# io.net
KiCad netlist of a schematic drawn in EAGLE
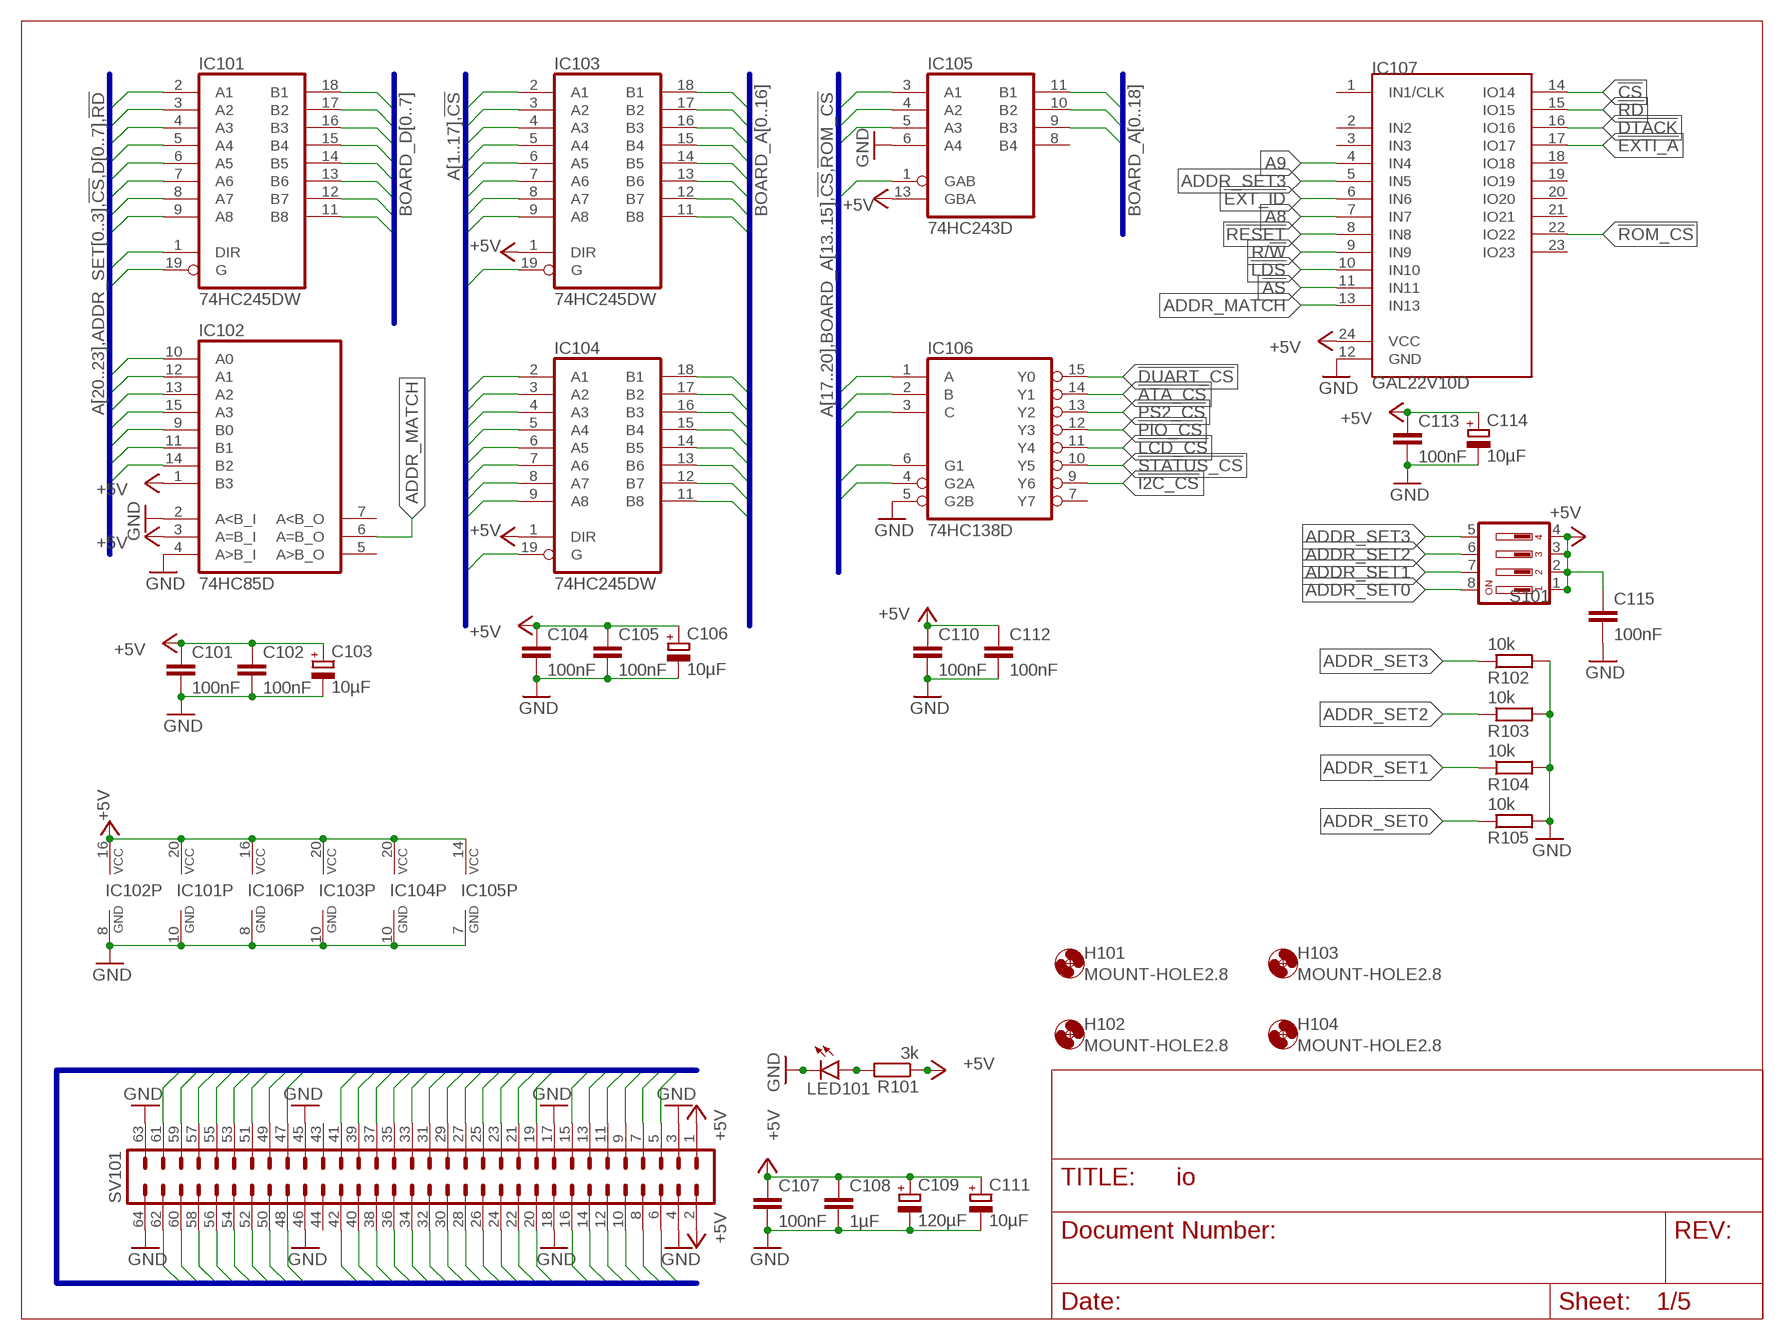
[diagram p0: schematic, sheet 1]
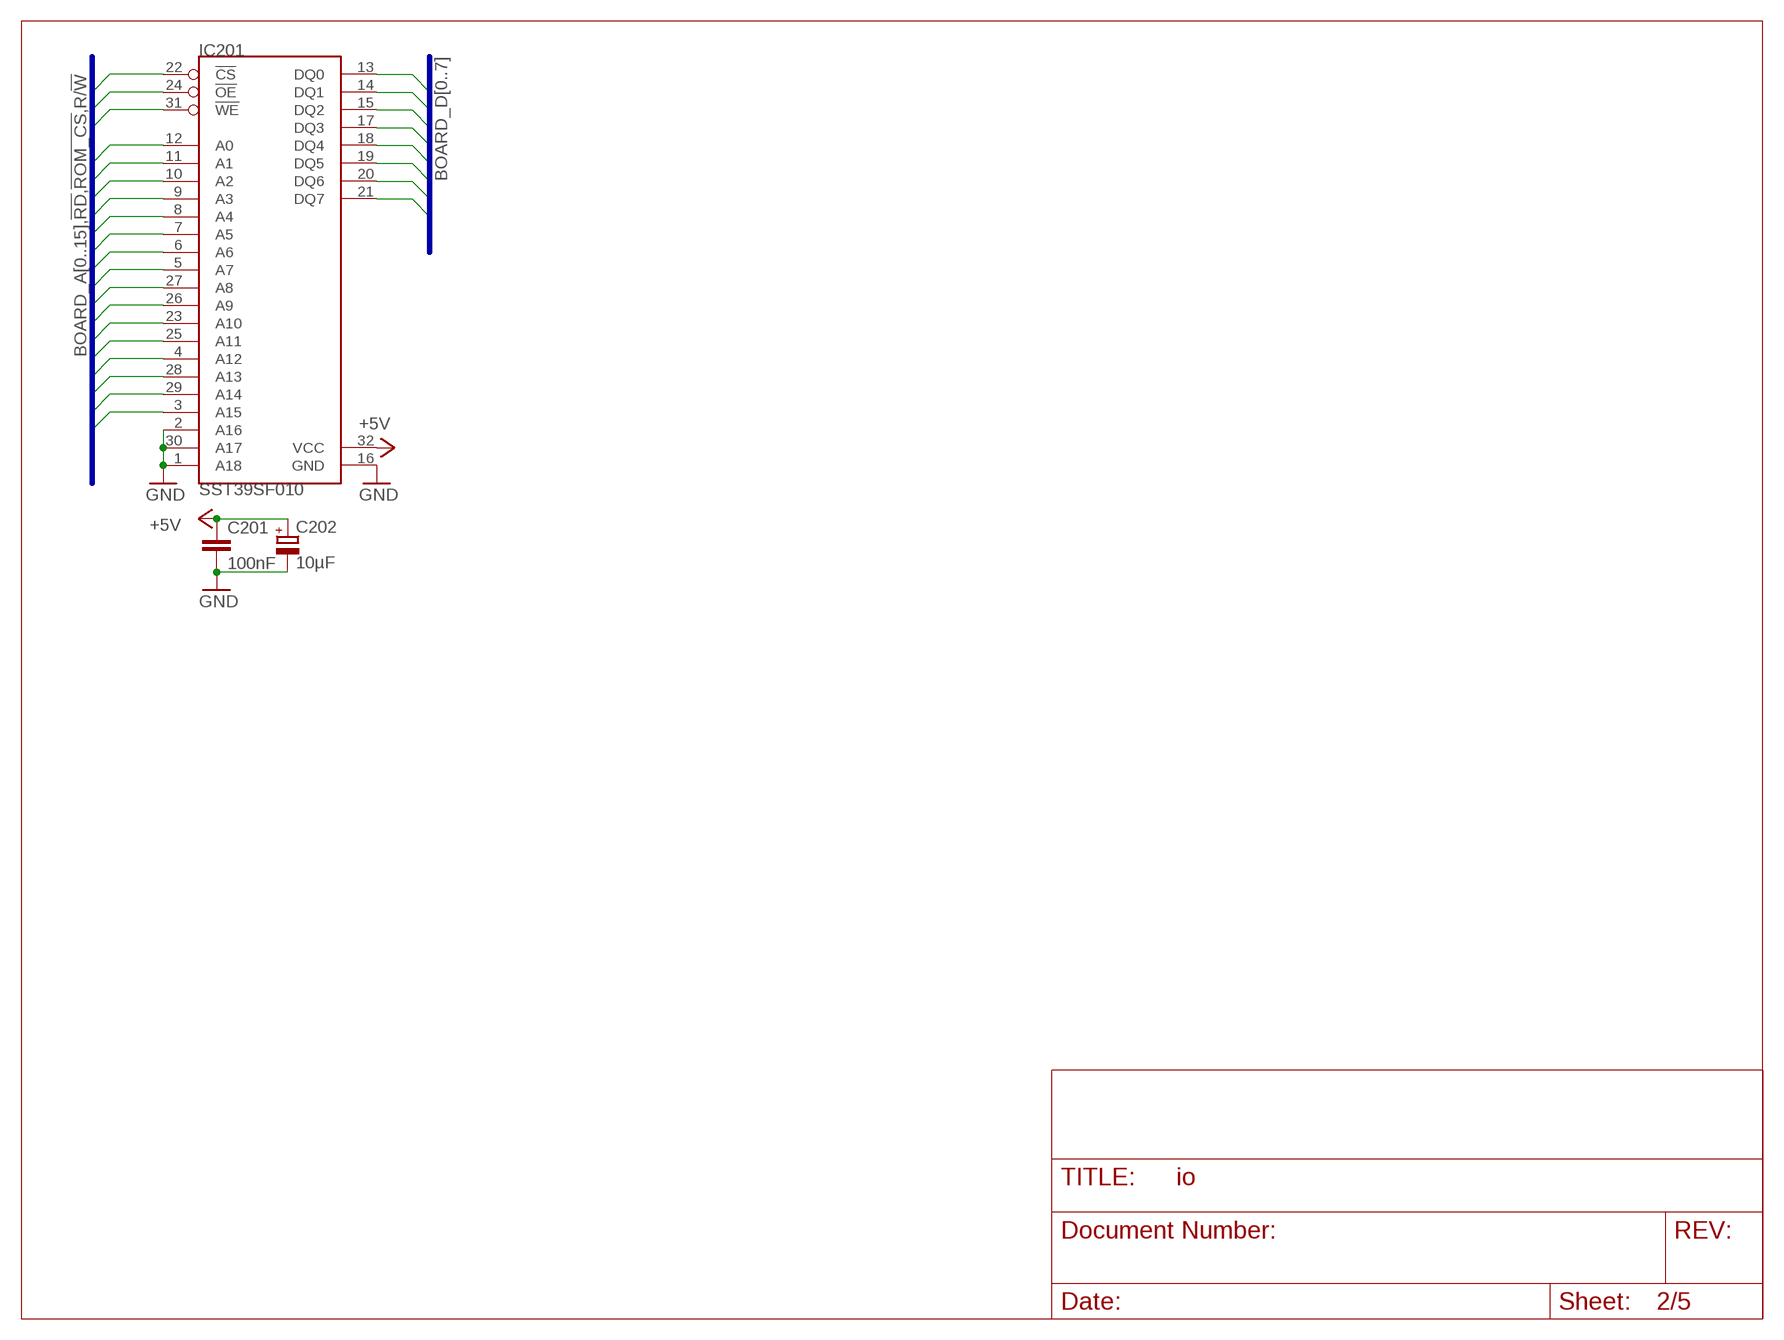
[diagram p1: schematic, sheet 2]
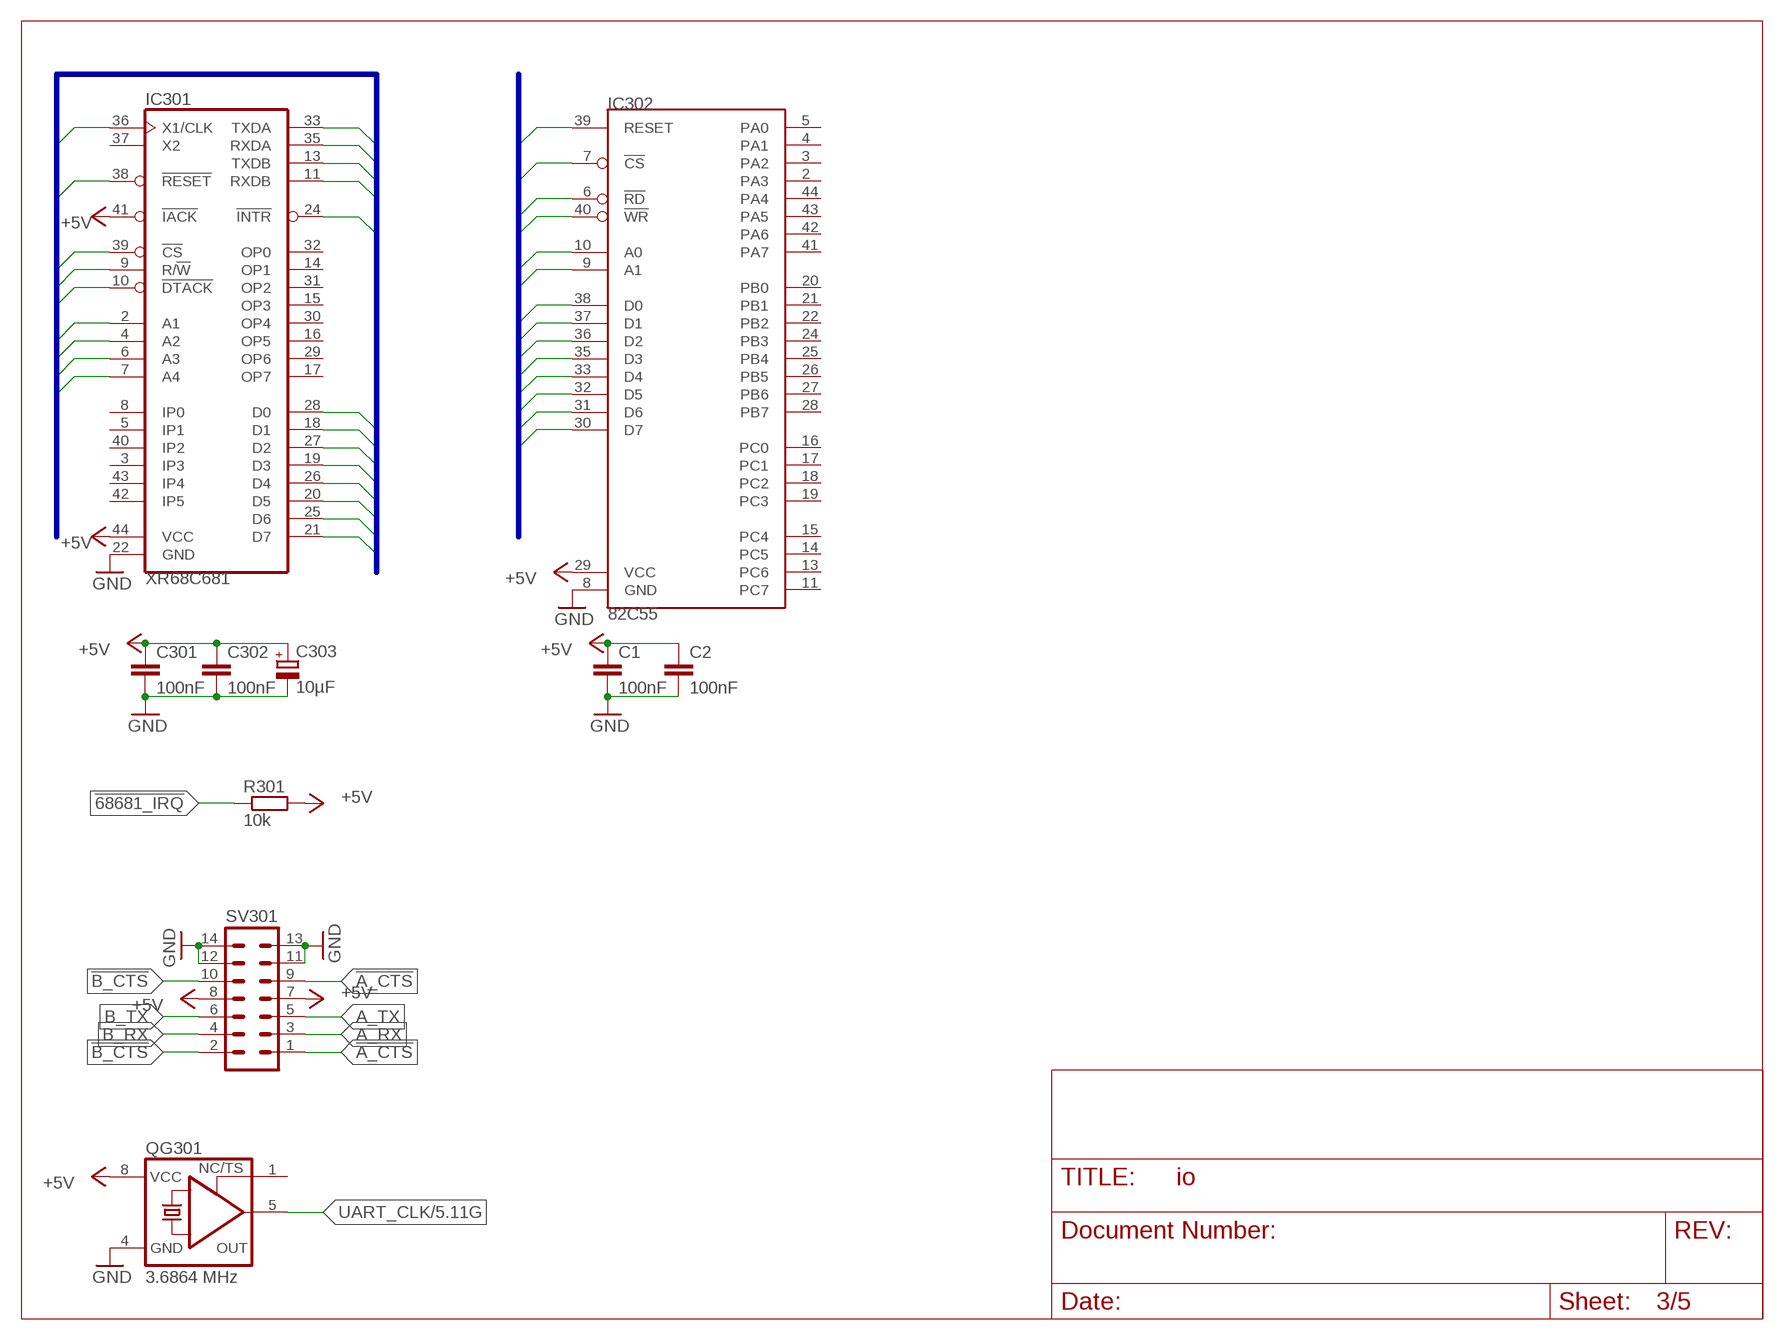
[diagram p2: schematic, sheet 3]
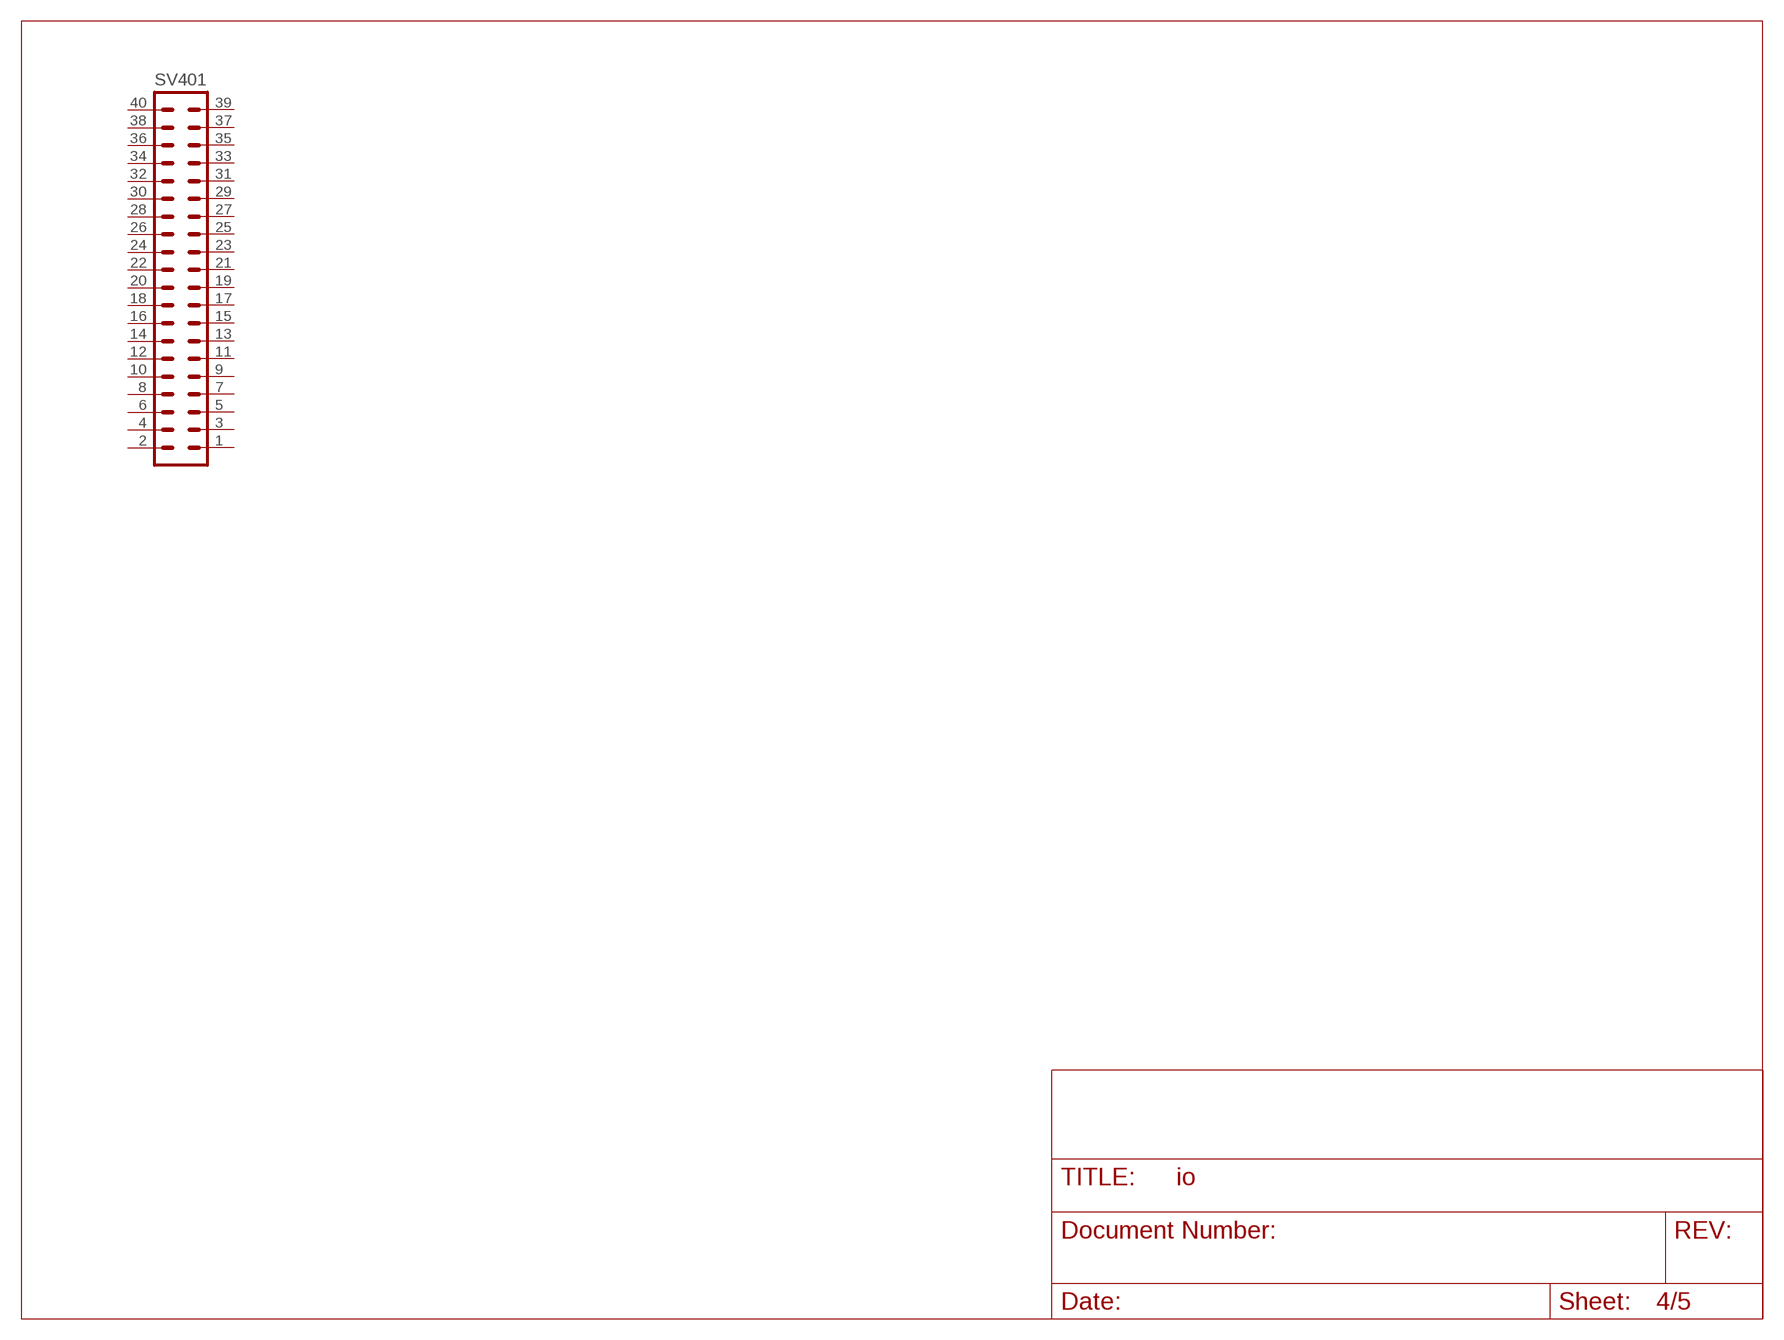
[diagram p3: schematic, sheet 4]
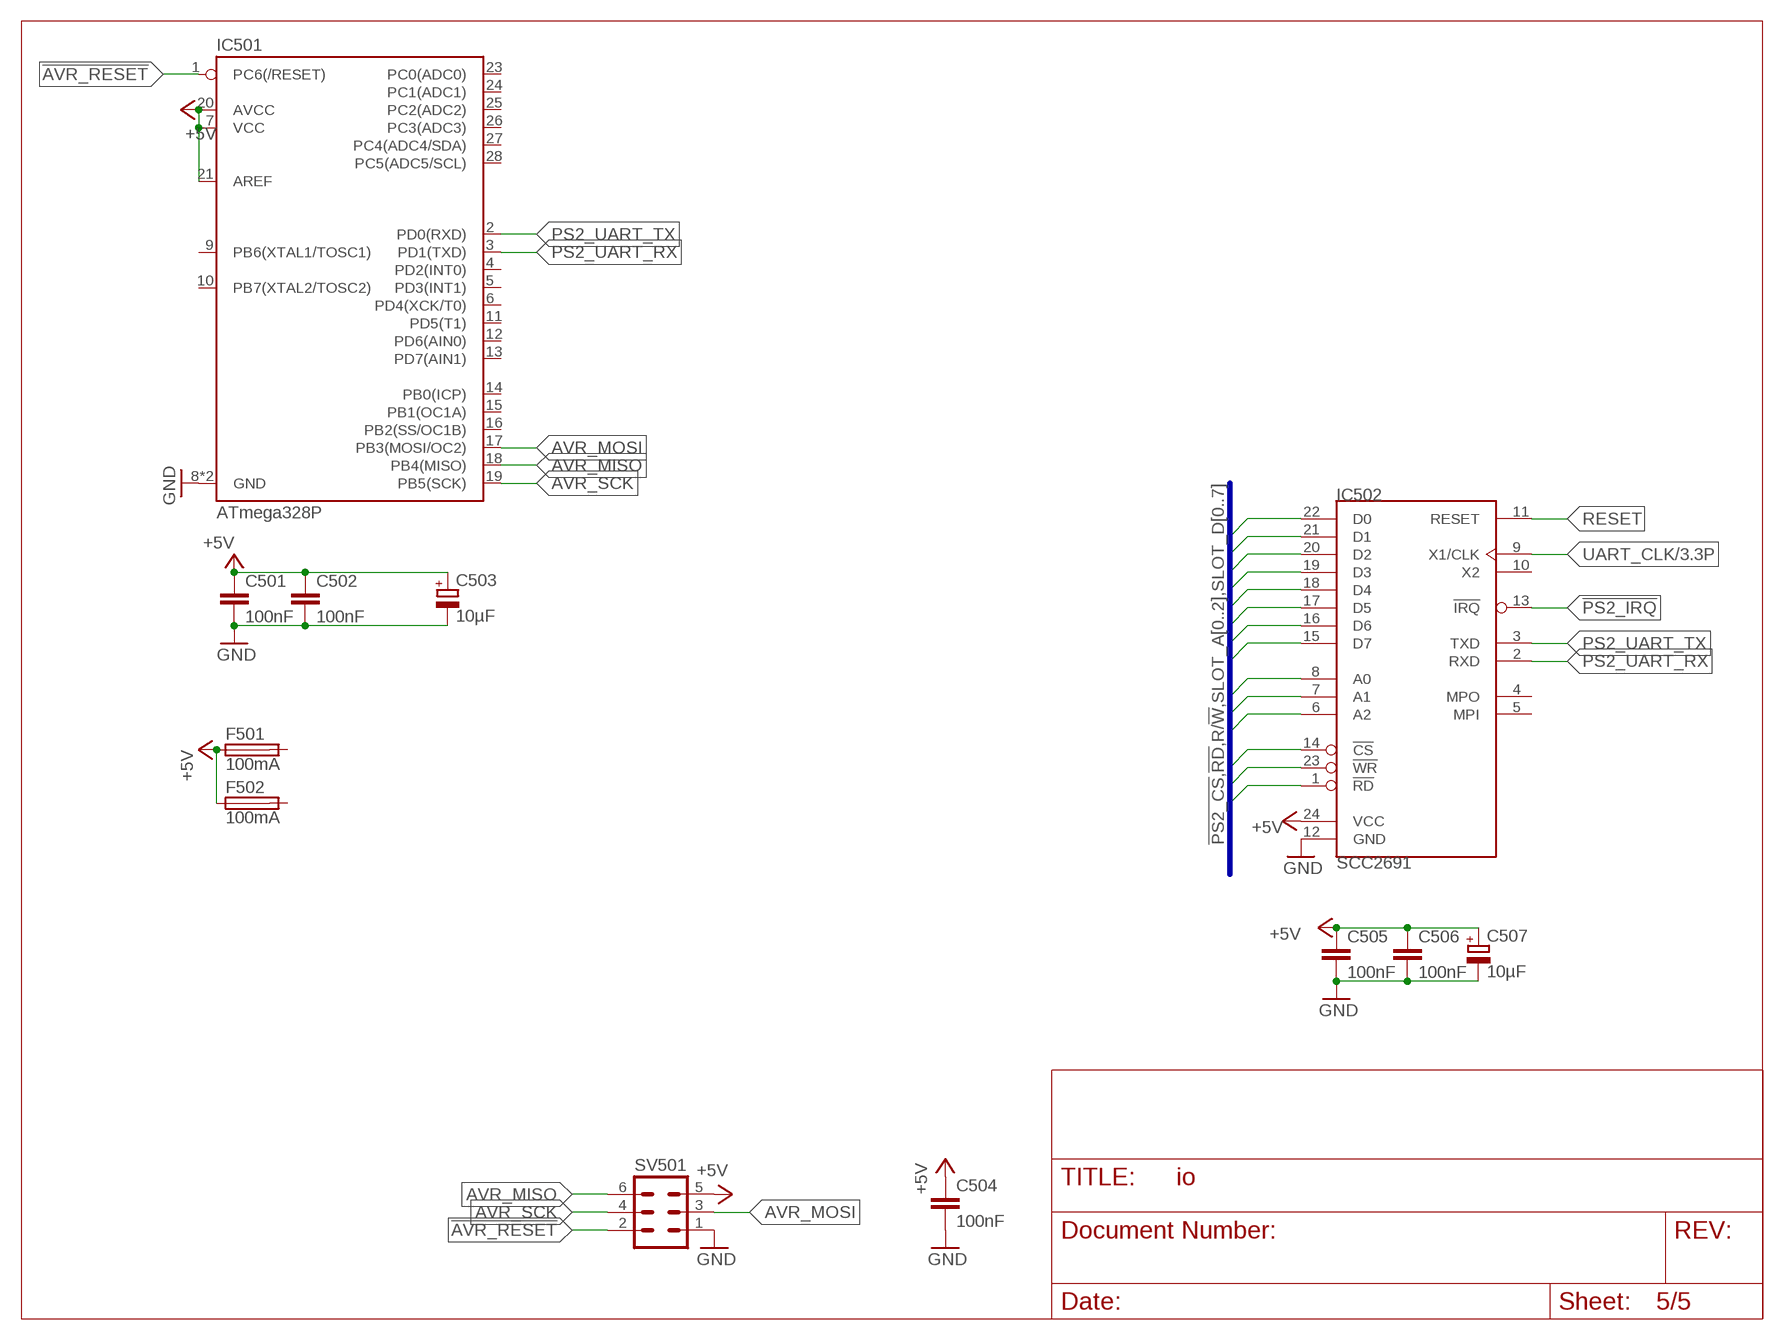
[diagram p4: schematic, sheet 5]

(export (version "E")
  (design (tool "Eeschema 10.0.6"))
  (components
    (comp (ref "C201")
      (value "100nF")
      (footprint "eagle-import:C0805")
      (libsource (lib "eagle-import") (part "C-EUC0805"))
    )
    (comp (ref "C202")
      (value "10µF")
      (footprint "eagle-import:SMC_B")
      (libsource (lib "eagle-import") (part "CPOL-EUSMCB"))
    )
    (comp (ref "IC201")
      (value "SST39SF010")
      (footprint "eagle-import:PLCC-S32")
      (libsource (lib "eagle-import") (part "SST39SF0X0PLCC32-SOCKET"))
    )
    (comp (ref "C1")
      (value "100nF")
      (footprint "eagle-import:C0805")
      (libsource (lib "eagle-import") (part "C-EUC0805"))
    )
    (comp (ref "C2")
      (value "100nF")
      (footprint "eagle-import:C0805")
      (libsource (lib "eagle-import") (part "C-EUC0805"))
    )
    (comp (ref "C301")
      (value "100nF")
      (footprint "eagle-import:C0805")
      (libsource (lib "eagle-import") (part "C-EUC0805"))
    )
    (comp (ref "C302")
      (value "100nF")
      (footprint "eagle-import:C0805")
      (libsource (lib "eagle-import") (part "C-EUC0805"))
    )
    (comp (ref "C303")
      (value "10µF")
      (footprint "eagle-import:SMC_B")
      (libsource (lib "eagle-import") (part "CPOL-EUSMCB"))
    )
    (comp (ref "IC301")
      (value "XR68C681")
      (footprint "eagle-import:PLCC-S44")
      (libsource (lib "eagle-import") (part "MC68681PLCC44-SOCKET"))
    )
    (comp (ref "IC302")
      (value "82C55")
      (footprint "eagle-import:PLCC-S44")
      (libsource (lib "eagle-import") (part "82C55PLCC44-SOCKET"))
    )
    (comp (ref "QG301")
      (value "3.6864 MHz")
      (footprint "eagle-import:DIL08S")
      (libsource (lib "eagle-import") (part "XO-8"))
    )
    (comp (ref "R301")
      (value "10k")
      (footprint "eagle-import:R2012")
      (libsource (lib "eagle-import") (part "R-EU_R2012"))
    )
    (comp (ref "SV301")
      (value "MA07-2W")
      (footprint "eagle-import:MA07-2W")
      (libsource (lib "eagle-import") (part "MA07-2W"))
    )
    (comp (ref "C101")
      (value "100nF")
      (footprint "eagle-import:C0805")
      (libsource (lib "eagle-import") (part "C-EUC0805"))
    )
    (comp (ref "C102")
      (value "100nF")
      (footprint "eagle-import:C0805")
      (libsource (lib "eagle-import") (part "C-EUC0805"))
    )
    (comp (ref "C103")
      (value "10µF")
      (footprint "eagle-import:SMC_B")
      (libsource (lib "eagle-import") (part "CPOL-EUSMCB"))
    )
    (comp (ref "C104")
      (value "100nF")
      (footprint "eagle-import:C0805")
      (libsource (lib "eagle-import") (part "C-EUC0805"))
    )
    (comp (ref "C105")
      (value "100nF")
      (footprint "eagle-import:C0805")
      (libsource (lib "eagle-import") (part "C-EUC0805"))
    )
    (comp (ref "C106")
      (value "10µF")
      (footprint "eagle-import:SMC_B")
      (libsource (lib "eagle-import") (part "CPOL-EUSMCB"))
    )
    (comp (ref "C107")
      (value "100nF")
      (footprint "eagle-import:C0805")
      (libsource (lib "eagle-import") (part "C-EUC0805"))
    )
    (comp (ref "C108")
      (value "1µF")
      (footprint "eagle-import:C0805")
      (libsource (lib "eagle-import") (part "C-EUC0805"))
    )
    (comp (ref "C109")
      (value "120µF")
      (footprint "eagle-import:E2,5-7")
      (libsource (lib "eagle-import") (part "CPOL-EUE2.5-7"))
    )
    (comp (ref "C110")
      (value "100nF")
      (footprint "eagle-import:C0805")
      (libsource (lib "eagle-import") (part "C-EUC0805"))
    )
    (comp (ref "C111")
      (value "10µF")
      (footprint "eagle-import:SMC_B")
      (libsource (lib "eagle-import") (part "CPOL-EUSMCB"))
    )
    (comp (ref "C112")
      (value "100nF")
      (footprint "eagle-import:C0805")
      (libsource (lib "eagle-import") (part "C-EUC0805"))
    )
    (comp (ref "C113")
      (value "100nF")
      (footprint "eagle-import:C0805")
      (libsource (lib "eagle-import") (part "C-EUC0805"))
    )
    (comp (ref "C114")
      (value "10µF")
      (footprint "eagle-import:SMC_B")
      (libsource (lib "eagle-import") (part "CPOL-EUSMCB"))
    )
    (comp (ref "C115")
      (value "100nF")
      (footprint "eagle-import:C0805")
      (libsource (lib "eagle-import") (part "C-EUC0805"))
    )
    (comp (ref "H101")
      (value "MOUNT-HOLE2.8")
      (footprint "eagle-import:2,8")
      (libsource (lib "eagle-import") (part "MOUNT-HOLE2.8"))
    )
    (comp (ref "H102")
      (value "MOUNT-HOLE2.8")
      (footprint "eagle-import:2,8")
      (libsource (lib "eagle-import") (part "MOUNT-HOLE2.8"))
    )
    (comp (ref "H103")
      (value "MOUNT-HOLE2.8")
      (footprint "eagle-import:2,8")
      (libsource (lib "eagle-import") (part "MOUNT-HOLE2.8"))
    )
    (comp (ref "H104")
      (value "MOUNT-HOLE2.8")
      (footprint "eagle-import:2,8")
      (libsource (lib "eagle-import") (part "MOUNT-HOLE2.8"))
    )
    (comp (ref "IC101")
      (value "74HC245DW")
      (footprint "eagle-import:SO20W")
      (fields (field (name "MOUSER") "595-SN74HC245DWR"))
      (libsource (lib "eagle-import") (part "74245DWHC"))
    )
    (comp (ref "IC102")
      (value "74HC85D")
      (footprint "eagle-import:SO16")
      (fields (field (name "MOUSER") "771-74HC138D"))
      (libsource (lib "eagle-import") (part "7485DHC"))
    )
    (comp (ref "IC103")
      (value "74HC245DW")
      (footprint "eagle-import:SO20W")
      (fields (field (name "MOUSER") "595-SN74HC245DWR"))
      (libsource (lib "eagle-import") (part "74245DWHC"))
    )
    (comp (ref "IC104")
      (value "74HC245DW")
      (footprint "eagle-import:SO20W")
      (fields (field (name "MOUSER") "595-SN74HC245DWR"))
      (libsource (lib "eagle-import") (part "74245DWHC"))
    )
    (comp (ref "IC105")
      (value "74HC243D")
      (footprint "eagle-import:SO14")
      (fields (field (name "MOUSER") "595-CD74HC243M96"))
      (libsource (lib "eagle-import") (part "74243DHC"))
    )
    (comp (ref "IC106")
      (value "74HC138D")
      (footprint "eagle-import:SO16")
      (fields (field (name "MOUSER") "595-SN74HC138DG4"))
      (libsource (lib "eagle-import") (part "74138DHC"))
    )
    (comp (ref "IC107")
      (value "GAL22V10D")
      (footprint "eagle-import:DIL24S")
      (libsource (lib "eagle-import") (part "GAL22V10DIP24"))
    )
    (comp (ref "LED101")
      (value "LEDCHIPLED_1206")
      (footprint "eagle-import:CHIPLED_1206")
      (libsource (lib "eagle-import") (part "LEDCHIPLED_1206"))
    )
    (comp (ref "R101")
      (value "3k")
      (footprint "eagle-import:R2012")
      (libsource (lib "eagle-import") (part "R-EU_R2012"))
    )
    (comp (ref "R102")
      (value "10k")
      (footprint "eagle-import:R2012")
      (libsource (lib "eagle-import") (part "R-EU_R2012"))
    )
    (comp (ref "R103")
      (value "10k")
      (footprint "eagle-import:R2012")
      (libsource (lib "eagle-import") (part "R-EU_R2012"))
    )
    (comp (ref "R104")
      (value "10k")
      (footprint "eagle-import:R2012")
      (libsource (lib "eagle-import") (part "R-EU_R2012"))
    )
    (comp (ref "R105")
      (value "10k")
      (footprint "eagle-import:R2012")
      (libsource (lib "eagle-import") (part "R-EU_R2012"))
    )
    (comp (ref "S101")
      (value "DP04")
      (footprint "eagle-import:DP-04")
      (libsource (lib "eagle-import") (part "DP04"))
    )
    (comp (ref "SV101")
      (value "ML64L")
      (footprint "eagle-import:ML64L")
      (libsource (lib "eagle-import") (part "ML64L"))
    )
    (comp (ref "C501")
      (value "100nF")
      (footprint "eagle-import:C0805")
      (libsource (lib "eagle-import") (part "C-EUC0805"))
    )
    (comp (ref "C502")
      (value "100nF")
      (footprint "eagle-import:C0805")
      (libsource (lib "eagle-import") (part "C-EUC0805"))
    )
    (comp (ref "C503")
      (value "10µF")
      (footprint "eagle-import:SMC_B")
      (libsource (lib "eagle-import") (part "CPOL-EUSMCB"))
    )
    (comp (ref "C504")
      (value "100nF")
      (footprint "eagle-import:C0805")
      (libsource (lib "eagle-import") (part "C-EUC0805"))
    )
    (comp (ref "C505")
      (value "100nF")
      (footprint "eagle-import:C0805")
      (libsource (lib "eagle-import") (part "C-EUC0805"))
    )
    (comp (ref "C506")
      (value "100nF")
      (footprint "eagle-import:C0805")
      (libsource (lib "eagle-import") (part "C-EUC0805"))
    )
    (comp (ref "C507")
      (value "10µF")
      (footprint "eagle-import:SMC_B")
      (libsource (lib "eagle-import") (part "CPOL-EUSMCB"))
    )
    (comp (ref "F501")
      (value "100mA")
      (footprint "eagle-import:WE-MI_1206")
      (libsource (lib "eagle-import") (part "FUSE1206"))
    )
    (comp (ref "F502")
      (value "100mA")
      (footprint "eagle-import:WE-MI_1206")
      (libsource (lib "eagle-import") (part "FUSE1206"))
    )
    (comp (ref "IC501")
      (value "ATmega328P")
      (footprint "eagle-import:DIP28")
      (libsource (lib "eagle-import") (part "ATMEGA328P_PDIP"))
    )
    (comp (ref "IC502")
      (value "SCC2691")
      (footprint "eagle-import:DIL24S")
      (libsource (lib "eagle-import") (part "SCC2691"))
    )
    (comp (ref "SV501")
      (value "ML6")
      (footprint "eagle-import:ML6")
      (libsource (lib "eagle-import") (part "ML6"))
    )
    (comp (ref "SV401")
      (value "ML40L")
      (footprint "eagle-import:ML40L")
      (libsource (lib "eagle-import") (part "ML40L"))
    )
  )
  (nets
    (net (code "4") (name "+5V") (class "Default")
      (node (ref "C1") (pin "1") (pinfunction "1_1") (pintype "passive"))
      (node (ref "C101") (pin "1") (pinfunction "1_1") (pintype "passive"))
      (node (ref "C102") (pin "1") (pinfunction "1_1") (pintype "passive"))
      (node (ref "C103") (pin "+") (pinfunction "+_+") (pintype "passive"))
      (node (ref "C104") (pin "1") (pinfunction "1_1") (pintype "passive"))
      (node (ref "C105") (pin "1") (pinfunction "1_1") (pintype "passive"))
      (node (ref "C106") (pin "+") (pinfunction "+_+") (pintype "passive"))
      (node (ref "C107") (pin "1") (pinfunction "1_1") (pintype "passive"))
      (node (ref "C108") (pin "1") (pinfunction "1_1") (pintype "passive"))
      (node (ref "C109") (pin "+") (pinfunction "+_+") (pintype "passive"))
      (node (ref "C110") (pin "1") (pinfunction "1_1") (pintype "passive"))
      (node (ref "C111") (pin "+") (pinfunction "+_+") (pintype "passive"))
      (node (ref "C112") (pin "1") (pinfunction "1_1") (pintype "passive"))
      (node (ref "C113") (pin "1") (pinfunction "1_1") (pintype "passive"))
      (node (ref "C114") (pin "+") (pinfunction "+_+") (pintype "passive"))
      (node (ref "C115") (pin "1") (pinfunction "1_1") (pintype "passive"))
      (node (ref "C2") (pin "1") (pinfunction "1_1") (pintype "passive"))
      (node (ref "C201") (pin "1") (pinfunction "1_1") (pintype "passive"))
      (node (ref "C202") (pin "+") (pinfunction "+_+") (pintype "passive"))
      (node (ref "C301") (pin "1") (pinfunction "1_1") (pintype "passive"))
      (node (ref "C302") (pin "1") (pinfunction "1_1") (pintype "passive"))
      (node (ref "C303") (pin "+") (pinfunction "+_+") (pintype "passive"))
      (node (ref "C501") (pin "1") (pinfunction "1_1") (pintype "passive"))
      (node (ref "C502") (pin "1") (pinfunction "1_1") (pintype "passive"))
      (node (ref "C503") (pin "+") (pinfunction "+_+") (pintype "passive"))
      (node (ref "C504") (pin "1") (pinfunction "1_1") (pintype "passive"))
      (node (ref "C505") (pin "1") (pinfunction "1_1") (pintype "passive"))
      (node (ref "C506") (pin "1") (pinfunction "1_1") (pintype "passive"))
      (node (ref "C507") (pin "+") (pinfunction "+_+") (pintype "passive"))
      (node (ref "F501") (pin "1") (pinfunction "1_1") (pintype "passive"))
      (node (ref "F502") (pin "1") (pinfunction "1_1") (pintype "passive"))
      (node (ref "IC101") (pin "20") (pinfunction "VCC_20") (pintype "power_in"))
      (node (ref "IC102") (pin "1") (pinfunction "B3_1") (pintype "input"))
      (node (ref "IC102") (pin "16") (pinfunction "VCC_16") (pintype "power_in"))
      (node (ref "IC102") (pin "3") (pinfunction "A=B_I_3") (pintype "input"))
      (node (ref "IC103") (pin "1") (pinfunction "DIR_1") (pintype "input"))
      (node (ref "IC103") (pin "20") (pinfunction "VCC_20") (pintype "power_in"))
      (node (ref "IC104") (pin "1") (pinfunction "DIR_1") (pintype "input"))
      (node (ref "IC104") (pin "20") (pinfunction "VCC_20") (pintype "power_in"))
      (node (ref "IC105") (pin "13") (pinfunction "GBA_13") (pintype "input"))
      (node (ref "IC105") (pin "14") (pinfunction "VCC_14") (pintype "power_in"))
      (node (ref "IC106") (pin "16") (pinfunction "VCC_16") (pintype "power_in"))
      (node (ref "IC107") (pin "24") (pinfunction "VCC_24") (pintype "power_in"))
      (node (ref "IC201") (pin "32") (pinfunction "VCC_32") (pintype "power_in"))
      (node (ref "IC301") (pin "41") (pinfunction "~{IACK}_41") (pintype "input"))
      (node (ref "IC301") (pin "44") (pinfunction "VCC_44") (pintype "power_in"))
      (node (ref "IC302") (pin "29") (pinfunction "VCC_29") (pintype "power_in"))
      (node (ref "IC501") (pin "20") (pinfunction "AVCC_20") (pintype "bidirectional"))
      (node (ref "IC501") (pin "21") (pinfunction "AREF_21") (pintype "bidirectional"))
      (node (ref "IC501") (pin "7") (pinfunction "VCC_7") (pintype "bidirectional"))
      (node (ref "IC502") (pin "24") (pinfunction "VCC_24") (pintype "power_in"))
      (node (ref "QG301") (pin "8") (pinfunction "VCC_8") (pintype "power_in"))
      (node (ref "R101") (pin "1") (pinfunction "1_1") (pintype "passive"))
      (node (ref "R301") (pin "2") (pinfunction "2_2") (pintype "passive"))
      (node (ref "S101") (pin "1") (pinfunction "1_1") (pintype "passive"))
      (node (ref "S101") (pin "2") (pinfunction "2_2") (pintype "passive"))
      (node (ref "S101") (pin "3") (pinfunction "3_3") (pintype "passive"))
      (node (ref "S101") (pin "4") (pinfunction "4_4") (pintype "passive"))
      (node (ref "SV101") (pin "1") (pinfunction "1_1") (pintype "passive"))
      (node (ref "SV101") (pin "2") (pinfunction "2_2") (pintype "passive"))
      (node (ref "SV301") (pin "7") (pinfunction "7_7") (pintype "passive"))
      (node (ref "SV301") (pin "8") (pinfunction "8_8") (pintype "passive"))
      (node (ref "SV501") (pin "5") (pinfunction "5_5") (pintype "passive"))
    )
    (net (code "14") (name "A1") (class "Default")
      (node (ref "IC103") (pin "2") (pinfunction "A1_2") (pintype "bidirectional"))
      (node (ref "SV101") (pin "20") (pinfunction "20_20") (pintype "passive"))
    )
    (net (code "15") (name "A2") (class "Default")
      (node (ref "IC103") (pin "3") (pinfunction "A2_3") (pintype "bidirectional"))
      (node (ref "SV101") (pin "22") (pinfunction "22_22") (pintype "passive"))
    )
    (net (code "16") (name "A3") (class "Default")
      (node (ref "IC103") (pin "4") (pinfunction "A3_4") (pintype "bidirectional"))
      (node (ref "SV101") (pin "19") (pinfunction "19_19") (pintype "passive"))
    )
    (net (code "17") (name "A4") (class "Default")
      (node (ref "IC103") (pin "5") (pinfunction "A4_5") (pintype "bidirectional"))
      (node (ref "SV101") (pin "24") (pinfunction "24_24") (pintype "passive"))
    )
    (net (code "18") (name "A5") (class "Default")
      (node (ref "IC103") (pin "6") (pinfunction "A5_6") (pintype "bidirectional"))
      (node (ref "SV101") (pin "21") (pinfunction "21_21") (pintype "passive"))
    )
    (net (code "19") (name "A6") (class "Default")
      (node (ref "IC103") (pin "7") (pinfunction "A6_7") (pintype "bidirectional"))
      (node (ref "SV101") (pin "23") (pinfunction "23_23") (pintype "passive"))
    )
    (net (code "20") (name "A7") (class "Default")
      (node (ref "IC103") (pin "8") (pinfunction "A7_8") (pintype "bidirectional"))
      (node (ref "SV101") (pin "26") (pinfunction "26_26") (pintype "passive"))
    )
    (net (code "21") (name "A8") (class "Default")
      (node (ref "IC103") (pin "9") (pinfunction "A8_9") (pintype "bidirectional"))
      (node (ref "IC107") (pin "7") (pinfunction "IN7_7") (pintype "input"))
      (node (ref "SV101") (pin "25") (pinfunction "25_25") (pintype "passive"))
    )
    (net (code "22") (name "A9") (class "Default")
      (node (ref "IC104") (pin "2") (pinfunction "A1_2") (pintype "bidirectional"))
      (node (ref "IC107") (pin "4") (pinfunction "IN4_4") (pintype "input"))
      (node (ref "SV101") (pin "28") (pinfunction "28_28") (pintype "passive"))
    )
    (net (code "23") (name "A10") (class "Default")
      (node (ref "IC104") (pin "3") (pinfunction "A2_3") (pintype "bidirectional"))
      (node (ref "SV101") (pin "27") (pinfunction "27_27") (pintype "passive"))
    )
    (net (code "24") (name "A11") (class "Default")
      (node (ref "IC104") (pin "4") (pinfunction "A3_4") (pintype "bidirectional"))
      (node (ref "SV101") (pin "30") (pinfunction "30_30") (pintype "passive"))
    )
    (net (code "25") (name "A12") (class "Default")
      (node (ref "IC104") (pin "5") (pinfunction "A4_5") (pintype "bidirectional"))
      (node (ref "SV101") (pin "29") (pinfunction "29_29") (pintype "passive"))
    )
    (net (code "26") (name "A13") (class "Default")
      (node (ref "IC104") (pin "6") (pinfunction "A5_6") (pintype "bidirectional"))
      (node (ref "SV101") (pin "31") (pinfunction "31_31") (pintype "passive"))
    )
    (net (code "27") (name "A14") (class "Default")
      (node (ref "IC104") (pin "7") (pinfunction "A6_7") (pintype "bidirectional"))
      (node (ref "SV101") (pin "32") (pinfunction "32_32") (pintype "passive"))
    )
    (net (code "28") (name "A15") (class "Default")
      (node (ref "IC104") (pin "8") (pinfunction "A7_8") (pintype "bidirectional"))
      (node (ref "SV101") (pin "33") (pinfunction "33_33") (pintype "passive"))
    )
    (net (code "29") (name "A16") (class "Default")
      (node (ref "IC104") (pin "9") (pinfunction "A8_9") (pintype "bidirectional"))
      (node (ref "SV101") (pin "34") (pinfunction "34_34") (pintype "passive"))
    )
    (net (code "30") (name "A17") (class "Default")
      (node (ref "IC105") (pin "3") (pinfunction "A1_3") (pintype "bidirectional"))
      (node (ref "SV101") (pin "36") (pinfunction "36_36") (pintype "passive"))
    )
    (net (code "31") (name "A18") (class "Default")
      (node (ref "IC105") (pin "4") (pinfunction "A2_4") (pintype "bidirectional"))
      (node (ref "SV101") (pin "35") (pinfunction "35_35") (pintype "passive"))
    )
    (net (code "32") (name "A19") (class "Default")
      (node (ref "IC105") (pin "5") (pinfunction "A3_5") (pintype "bidirectional"))
      (node (ref "SV101") (pin "38") (pinfunction "38_38") (pintype "passive"))
    )
    (net (code "33") (name "A20") (class "Default")
      (node (ref "IC102") (pin "10") (pinfunction "A0_10") (pintype "input"))
      (node (ref "SV101") (pin "37") (pinfunction "37_37") (pintype "passive"))
    )
    (net (code "34") (name "A21") (class "Default")
      (node (ref "IC102") (pin "12") (pinfunction "A1_12") (pintype "input"))
      (node (ref "SV101") (pin "40") (pinfunction "40_40") (pintype "passive"))
    )
    (net (code "35") (name "A22") (class "Default")
      (node (ref "IC102") (pin "13") (pinfunction "A2_13") (pintype "input"))
      (node (ref "SV101") (pin "39") (pinfunction "39_39") (pintype "passive"))
    )
    (net (code "36") (name "A23") (class "Default")
      (node (ref "IC102") (pin "15") (pinfunction "A3_15") (pintype "input"))
      (node (ref "SV101") (pin "42") (pinfunction "42_42") (pintype "passive"))
    )
    (net (code "37") (name "ADDR_MATCH") (class "Default")
      (node (ref "IC102") (pin "6") (pinfunction "A=B_O_6") (pintype "output"))
      (node (ref "IC107") (pin "13") (pinfunction "IN13_13") (pintype "input"))
    )
    (net (code "38") (name "ADDR_SET0") (class "Default")
      (node (ref "IC102") (pin "9") (pinfunction "B0_9") (pintype "input"))
      (node (ref "R105") (pin "1") (pinfunction "1_1") (pintype "passive"))
      (node (ref "S101") (pin "8") (pinfunction "8_8") (pintype "passive"))
    )
    (net (code "39") (name "ADDR_SET1") (class "Default")
      (node (ref "IC102") (pin "11") (pinfunction "B1_11") (pintype "input"))
      (node (ref "R104") (pin "1") (pinfunction "1_1") (pintype "passive"))
      (node (ref "S101") (pin "7") (pinfunction "7_7") (pintype "passive"))
    )
    (net (code "40") (name "ADDR_SET2") (class "Default")
      (node (ref "IC102") (pin "14") (pinfunction "B2_14") (pintype "input"))
      (node (ref "R103") (pin "1") (pinfunction "1_1") (pintype "passive"))
      (node (ref "S101") (pin "6") (pinfunction "6_6") (pintype "passive"))
    )
    (net (code "41") (name "ADDR_SET3") (class "Default")
      (node (ref "IC107") (pin "5") (pinfunction "IN5_5") (pintype "input"))
      (node (ref "R102") (pin "1") (pinfunction "1_1") (pintype "passive"))
      (node (ref "S101") (pin "5") (pinfunction "5_5") (pintype "passive"))
    )
    (net (code "42") (name "AVR_MISO") (class "Default")
      (node (ref "IC501") (pin "18") (pinfunction "PB4(MISO)_18") (pintype "bidirectional"))
      (node (ref "SV501") (pin "6") (pinfunction "6_6") (pintype "passive"))
    )
    (net (code "43") (name "AVR_MOSI") (class "Default")
      (node (ref "IC501") (pin "17") (pinfunction "PB3(MOSI/OC2)_17") (pintype "bidirectional"))
      (node (ref "SV501") (pin "3") (pinfunction "3_3") (pintype "passive"))
    )
    (net (code "44") (name "AVR_SCK") (class "Default")
      (node (ref "IC501") (pin "19") (pinfunction "PB5(SCK)_19") (pintype "bidirectional"))
      (node (ref "SV501") (pin "4") (pinfunction "4_4") (pintype "passive"))
    )
    (net (code "45") (name "A_RX") (class "Default")
      (node (ref "IC301") (pin "35") (pinfunction "RXDA_35") (pintype "input"))
      (node (ref "SV301") (pin "3") (pinfunction "3_3") (pintype "passive"))
    )
    (net (code "46") (name "A_TX") (class "Default")
      (node (ref "IC301") (pin "33") (pinfunction "TXDA_33") (pintype "output"))
      (node (ref "SV301") (pin "5") (pinfunction "5_5") (pintype "passive"))
    )
    (net (code "47") (name "BOARD_A0") (class "Default")
      (node (ref "IC103") (pin "18") (pinfunction "B1_18") (pintype "bidirectional"))
      (node (ref "IC201") (pin "12") (pinfunction "A0_12") (pintype "input"))
      (node (ref "IC301") (pin "2") (pinfunction "A1_2") (pintype "input"))
      (node (ref "IC302") (pin "10") (pinfunction "A0_10") (pintype "input"))
    )
    (net (code "48") (name "BOARD_A1") (class "Default")
      (node (ref "IC103") (pin "17") (pinfunction "B2_17") (pintype "bidirectional"))
      (node (ref "IC201") (pin "11") (pinfunction "A1_11") (pintype "input"))
      (node (ref "IC301") (pin "4") (pinfunction "A2_4") (pintype "input"))
      (node (ref "IC302") (pin "9") (pinfunction "A1_9") (pintype "input"))
    )
    (net (code "49") (name "BOARD_A2") (class "Default")
      (node (ref "IC103") (pin "16") (pinfunction "B3_16") (pintype "bidirectional"))
      (node (ref "IC201") (pin "10") (pinfunction "A2_10") (pintype "input"))
      (node (ref "IC301") (pin "6") (pinfunction "A3_6") (pintype "input"))
    )
    (net (code "50") (name "BOARD_A3") (class "Default")
      (node (ref "IC103") (pin "15") (pinfunction "B4_15") (pintype "bidirectional"))
      (node (ref "IC201") (pin "9") (pinfunction "A3_9") (pintype "input"))
      (node (ref "IC301") (pin "7") (pinfunction "A4_7") (pintype "input"))
    )
    (net (code "51") (name "BOARD_A4") (class "Default")
      (node (ref "IC103") (pin "14") (pinfunction "B5_14") (pintype "bidirectional"))
      (node (ref "IC201") (pin "8") (pinfunction "A4_8") (pintype "input"))
    )
    (net (code "52") (name "BOARD_A5") (class "Default")
      (node (ref "IC103") (pin "13") (pinfunction "B6_13") (pintype "bidirectional"))
      (node (ref "IC201") (pin "7") (pinfunction "A5_7") (pintype "input"))
    )
    (net (code "53") (name "BOARD_A6") (class "Default")
      (node (ref "IC103") (pin "12") (pinfunction "B7_12") (pintype "bidirectional"))
      (node (ref "IC201") (pin "6") (pinfunction "A6_6") (pintype "input"))
    )
    (net (code "54") (name "BOARD_A7") (class "Default")
      (node (ref "IC103") (pin "11") (pinfunction "B8_11") (pintype "bidirectional"))
      (node (ref "IC201") (pin "5") (pinfunction "A7_5") (pintype "input"))
    )
    (net (code "55") (name "BOARD_A8") (class "Default")
      (node (ref "IC104") (pin "18") (pinfunction "B1_18") (pintype "bidirectional"))
      (node (ref "IC201") (pin "27") (pinfunction "A8_27") (pintype "input"))
    )
    (net (code "56") (name "BOARD_A9") (class "Default")
      (node (ref "IC104") (pin "17") (pinfunction "B2_17") (pintype "bidirectional"))
      (node (ref "IC201") (pin "26") (pinfunction "A9_26") (pintype "input"))
    )
    (net (code "57") (name "BOARD_A10") (class "Default")
      (node (ref "IC104") (pin "16") (pinfunction "B3_16") (pintype "bidirectional"))
      (node (ref "IC201") (pin "23") (pinfunction "A10_23") (pintype "input"))
    )
    (net (code "58") (name "BOARD_A11") (class "Default")
      (node (ref "IC104") (pin "15") (pinfunction "B4_15") (pintype "bidirectional"))
      (node (ref "IC201") (pin "25") (pinfunction "A11_25") (pintype "input"))
    )
    (net (code "59") (name "BOARD_A12") (class "Default")
      (node (ref "IC104") (pin "14") (pinfunction "B5_14") (pintype "bidirectional"))
      (node (ref "IC201") (pin "4") (pinfunction "A12_4") (pintype "input"))
    )
    (net (code "60") (name "BOARD_A13") (class "Default")
      (node (ref "IC104") (pin "13") (pinfunction "B6_13") (pintype "bidirectional"))
      (node (ref "IC106") (pin "1") (pinfunction "A_1") (pintype "input"))
      (node (ref "IC201") (pin "28") (pinfunction "A13_28") (pintype "input"))
    )
    (net (code "61") (name "BOARD_A14") (class "Default")
      (node (ref "IC104") (pin "12") (pinfunction "B7_12") (pintype "bidirectional"))
      (node (ref "IC106") (pin "2") (pinfunction "B_2") (pintype "input"))
      (node (ref "IC201") (pin "29") (pinfunction "A14_29") (pintype "input"))
    )
    (net (code "62") (name "BOARD_A15") (class "Default")
      (node (ref "IC104") (pin "11") (pinfunction "B8_11") (pintype "bidirectional"))
      (node (ref "IC106") (pin "3") (pinfunction "C_3") (pintype "input"))
      (node (ref "IC201") (pin "3") (pinfunction "A15_3") (pintype "input"))
    )
    (net (code "63") (name "BOARD_D0") (class "Default")
      (node (ref "IC101") (pin "18") (pinfunction "B1_18") (pintype "bidirectional"))
      (node (ref "IC201") (pin "13") (pinfunction "DQ0_13") (pintype "bidirectional"))
      (node (ref "IC301") (pin "28") (pinfunction "D0_28") (pintype "bidirectional"))
      (node (ref "IC302") (pin "38") (pinfunction "D0_38") (pintype "bidirectional"))
    )
    (net (code "64") (name "BOARD_D1") (class "Default")
      (node (ref "IC101") (pin "17") (pinfunction "B2_17") (pintype "bidirectional"))
      (node (ref "IC201") (pin "14") (pinfunction "DQ1_14") (pintype "bidirectional"))
      (node (ref "IC301") (pin "18") (pinfunction "D1_18") (pintype "bidirectional"))
      (node (ref "IC302") (pin "37") (pinfunction "D1_37") (pintype "bidirectional"))
    )
    (net (code "65") (name "BOARD_D2") (class "Default")
      (node (ref "IC101") (pin "16") (pinfunction "B3_16") (pintype "bidirectional"))
      (node (ref "IC201") (pin "15") (pinfunction "DQ2_15") (pintype "bidirectional"))
      (node (ref "IC301") (pin "27") (pinfunction "D2_27") (pintype "bidirectional"))
      (node (ref "IC302") (pin "36") (pinfunction "D2_36") (pintype "bidirectional"))
    )
    (net (code "66") (name "BOARD_D3") (class "Default")
      (node (ref "IC101") (pin "15") (pinfunction "B4_15") (pintype "bidirectional"))
      (node (ref "IC201") (pin "17") (pinfunction "DQ3_17") (pintype "bidirectional"))
      (node (ref "IC301") (pin "19") (pinfunction "D3_19") (pintype "bidirectional"))
      (node (ref "IC302") (pin "35") (pinfunction "D3_35") (pintype "bidirectional"))
    )
    (net (code "67") (name "BOARD_D4") (class "Default")
      (node (ref "IC101") (pin "14") (pinfunction "B5_14") (pintype "bidirectional"))
      (node (ref "IC201") (pin "18") (pinfunction "DQ4_18") (pintype "bidirectional"))
      (node (ref "IC301") (pin "26") (pinfunction "D4_26") (pintype "bidirectional"))
      (node (ref "IC302") (pin "33") (pinfunction "D4_33") (pintype "bidirectional"))
    )
    (net (code "68") (name "BOARD_D5") (class "Default")
      (node (ref "IC101") (pin "13") (pinfunction "B6_13") (pintype "bidirectional"))
      (node (ref "IC201") (pin "19") (pinfunction "DQ5_19") (pintype "bidirectional"))
      (node (ref "IC301") (pin "20") (pinfunction "D5_20") (pintype "bidirectional"))
      (node (ref "IC302") (pin "32") (pinfunction "D5_32") (pintype "bidirectional"))
    )
    (net (code "69") (name "BOARD_D6") (class "Default")
      (node (ref "IC101") (pin "12") (pinfunction "B7_12") (pintype "bidirectional"))
      (node (ref "IC201") (pin "20") (pinfunction "DQ6_20") (pintype "bidirectional"))
      (node (ref "IC301") (pin "25") (pinfunction "D6_25") (pintype "bidirectional"))
      (node (ref "IC302") (pin "31") (pinfunction "D6_31") (pintype "bidirectional"))
    )
    (net (code "70") (name "BOARD_D7") (class "Default")
      (node (ref "IC101") (pin "11") (pinfunction "B8_11") (pintype "bidirectional"))
      (node (ref "IC201") (pin "21") (pinfunction "DQ7_21") (pintype "bidirectional"))
      (node (ref "IC301") (pin "21") (pinfunction "D7_21") (pintype "bidirectional"))
      (node (ref "IC302") (pin "30") (pinfunction "D7_30") (pintype "bidirectional"))
    )
    (net (code "71") (name "B_RX") (class "Default")
      (node (ref "IC301") (pin "11") (pinfunction "RXDB_11") (pintype "output"))
      (node (ref "SV301") (pin "4") (pinfunction "4_4") (pintype "passive"))
    )
    (net (code "72") (name "B_TX") (class "Default")
      (node (ref "IC301") (pin "13") (pinfunction "TXDB_13") (pintype "bidirectional"))
      (node (ref "SV301") (pin "6") (pinfunction "6_6") (pintype "passive"))
    )
    (net (code "73") (name "D0") (class "Default")
      (node (ref "IC101") (pin "2") (pinfunction "A1_2") (pintype "bidirectional"))
      (node (ref "SV101") (pin "62") (pinfunction "62_62") (pintype "passive"))
    )
    (net (code "74") (name "D1") (class "Default")
      (node (ref "IC101") (pin "3") (pinfunction "A2_3") (pintype "bidirectional"))
      (node (ref "SV101") (pin "60") (pinfunction "60_60") (pintype "passive"))
    )
    (net (code "75") (name "D2") (class "Default")
      (node (ref "IC101") (pin "4") (pinfunction "A3_4") (pintype "bidirectional"))
      (node (ref "SV101") (pin "58") (pinfunction "58_58") (pintype "passive"))
    )
    (net (code "76") (name "D3") (class "Default")
      (node (ref "IC101") (pin "5") (pinfunction "A4_5") (pintype "bidirectional"))
      (node (ref "SV101") (pin "56") (pinfunction "56_56") (pintype "passive"))
    )
    (net (code "77") (name "D4") (class "Default")
      (node (ref "IC101") (pin "6") (pinfunction "A5_6") (pintype "bidirectional"))
      (node (ref "SV101") (pin "54") (pinfunction "54_54") (pintype "passive"))
    )
    (net (code "78") (name "D5") (class "Default")
      (node (ref "IC101") (pin "7") (pinfunction "A6_7") (pintype "bidirectional"))
      (node (ref "SV101") (pin "52") (pinfunction "52_52") (pintype "passive"))
    )
    (net (code "79") (name "D6") (class "Default")
      (node (ref "IC101") (pin "8") (pinfunction "A7_8") (pintype "bidirectional"))
      (node (ref "SV101") (pin "50") (pinfunction "50_50") (pintype "passive"))
    )
    (net (code "80") (name "D7") (class "Default")
      (node (ref "IC101") (pin "9") (pinfunction "A8_9") (pintype "bidirectional"))
      (node (ref "SV101") (pin "48") (pinfunction "48_48") (pintype "passive"))
    )
    (net (code "81") (name "GND") (class "Default")
      (node (ref "C1") (pin "2") (pinfunction "2_2") (pintype "passive"))
      (node (ref "C101") (pin "2") (pinfunction "2_2") (pintype "passive"))
      (node (ref "C102") (pin "2") (pinfunction "2_2") (pintype "passive"))
      (node (ref "C103") (pin "-") (pinfunction "-_-") (pintype "passive"))
      (node (ref "C104") (pin "2") (pinfunction "2_2") (pintype "passive"))
      (node (ref "C105") (pin "2") (pinfunction "2_2") (pintype "passive"))
      (node (ref "C106") (pin "-") (pinfunction "-_-") (pintype "passive"))
      (node (ref "C107") (pin "2") (pinfunction "2_2") (pintype "passive"))
      (node (ref "C108") (pin "2") (pinfunction "2_2") (pintype "passive"))
      (node (ref "C109") (pin "-") (pinfunction "-_-") (pintype "passive"))
      (node (ref "C110") (pin "2") (pinfunction "2_2") (pintype "passive"))
      (node (ref "C111") (pin "-") (pinfunction "-_-") (pintype "passive"))
      (node (ref "C112") (pin "2") (pinfunction "2_2") (pintype "passive"))
      (node (ref "C113") (pin "2") (pinfunction "2_2") (pintype "passive"))
      (node (ref "C114") (pin "-") (pinfunction "-_-") (pintype "passive"))
      (node (ref "C115") (pin "2") (pinfunction "2_2") (pintype "passive"))
      (node (ref "C2") (pin "2") (pinfunction "2_2") (pintype "passive"))
      (node (ref "C201") (pin "2") (pinfunction "2_2") (pintype "passive"))
      (node (ref "C202") (pin "-") (pinfunction "-_-") (pintype "passive"))
      (node (ref "C301") (pin "2") (pinfunction "2_2") (pintype "passive"))
      (node (ref "C302") (pin "2") (pinfunction "2_2") (pintype "passive"))
      (node (ref "C303") (pin "-") (pinfunction "-_-") (pintype "passive"))
      (node (ref "C501") (pin "2") (pinfunction "2_2") (pintype "passive"))
      (node (ref "C502") (pin "2") (pinfunction "2_2") (pintype "passive"))
      (node (ref "C503") (pin "-") (pinfunction "-_-") (pintype "passive"))
      (node (ref "C504") (pin "2") (pinfunction "2_2") (pintype "passive"))
      (node (ref "C505") (pin "2") (pinfunction "2_2") (pintype "passive"))
      (node (ref "C506") (pin "2") (pinfunction "2_2") (pintype "passive"))
      (node (ref "C507") (pin "-") (pinfunction "-_-") (pintype "passive"))
      (node (ref "IC101") (pin "10") (pinfunction "GND_10") (pintype "power_in"))
      (node (ref "IC102") (pin "2") (pinfunction "A<B_I_2") (pintype "input"))
      (node (ref "IC102") (pin "4") (pinfunction "A>B_I_4") (pintype "input"))
      (node (ref "IC102") (pin "8") (pinfunction "GND_8") (pintype "power_in"))
      (node (ref "IC103") (pin "10") (pinfunction "GND_10") (pintype "power_in"))
      (node (ref "IC104") (pin "10") (pinfunction "GND_10") (pintype "power_in"))
      (node (ref "IC105") (pin "6") (pinfunction "A4_6") (pintype "bidirectional"))
      (node (ref "IC105") (pin "7") (pinfunction "GND_7") (pintype "power_in"))
      (node (ref "IC106") (pin "5") (pinfunction "G2B_5") (pintype "input"))
      (node (ref "IC106") (pin "8") (pinfunction "GND_8") (pintype "power_in"))
      (node (ref "IC107") (pin "12") (pinfunction "GND_12") (pintype "power_in"))
      (node (ref "IC201") (pin "1") (pinfunction "A18_1") (pintype "input"))
      (node (ref "IC201") (pin "16") (pinfunction "GND_16") (pintype "power_in"))
      (node (ref "IC201") (pin "2") (pinfunction "A16_2") (pintype "input"))
      (node (ref "IC201") (pin "30") (pinfunction "A17_30") (pintype "input"))
      (node (ref "IC301") (pin "22") (pinfunction "GND_22") (pintype "power_in"))
      (node (ref "IC302") (pin "8") (pinfunction "GND_8") (pintype "power_in"))
      (node (ref "IC501") (pin "22") (pinfunction "GND_22") (pintype "bidirectional"))
      (node (ref "IC501") (pin "8") (pinfunction "GND_8") (pintype "bidirectional"))
      (node (ref "IC502") (pin "12") (pinfunction "GND_12") (pintype "power_in"))
      (node (ref "LED101") (pin "C") (pinfunction "C_C") (pintype "passive"))
      (node (ref "QG301") (pin "4") (pinfunction "GND_4") (pintype "power_in"))
      (node (ref "R102") (pin "2") (pinfunction "2_2") (pintype "passive"))
      (node (ref "R103") (pin "2") (pinfunction "2_2") (pintype "passive"))
      (node (ref "R104") (pin "2") (pinfunction "2_2") (pintype "passive"))
      (node (ref "R105") (pin "2") (pinfunction "2_2") (pintype "passive"))
      (node (ref "SV101") (pin "17") (pinfunction "17_17") (pintype "passive"))
      (node (ref "SV101") (pin "18") (pinfunction "18_18") (pintype "passive"))
      (node (ref "SV101") (pin "3") (pinfunction "3_3") (pintype "passive"))
      (node (ref "SV101") (pin "4") (pinfunction "4_4") (pintype "passive"))
      (node (ref "SV101") (pin "45") (pinfunction "45_45") (pintype "passive"))
      (node (ref "SV101") (pin "46") (pinfunction "46_46") (pintype "passive"))
      (node (ref "SV101") (pin "63") (pinfunction "63_63") (pintype "passive"))
      (node (ref "SV101") (pin "64") (pinfunction "64_64") (pintype "passive"))
      (node (ref "SV301") (pin "11") (pinfunction "11_11") (pintype "passive"))
      (node (ref "SV301") (pin "12") (pinfunction "12_12") (pintype "passive"))
      (node (ref "SV301") (pin "13") (pinfunction "13_13") (pintype "passive"))
      (node (ref "SV301") (pin "14") (pinfunction "14_14") (pintype "passive"))
      (node (ref "SV501") (pin "1") (pinfunction "1_1") (pintype "passive"))
    )
    (net (code "82") (name "Net-(LED101-PadA)") (class "Default")
      (node (ref "LED101") (pin "A") (pinfunction "A_A") (pintype "passive"))
      (node (ref "R101") (pin "2") (pinfunction "2_2") (pintype "passive"))
    )
    (net (code "83") (name "PS2_UART_RX") (class "Default")
      (node (ref "IC501") (pin "3") (pinfunction "PD1(TXD)_3") (pintype "bidirectional"))
      (node (ref "IC502") (pin "2") (pinfunction "RXD_2") (pintype "input"))
    )
    (net (code "84") (name "PS2_UART_TX") (class "Default")
      (node (ref "IC501") (pin "2") (pinfunction "PD0(RXD)_2") (pintype "bidirectional"))
      (node (ref "IC502") (pin "3") (pinfunction "TXD_3") (pintype "output"))
    )
    (net (code "85") (name "RESET") (class "Default")
      (node (ref "IC302") (pin "39") (pinfunction "RESET_39") (pintype "input"))
      (node (ref "IC502") (pin "11") (pinfunction "RESET_11") (pintype "input"))
    )
    (net (code "86") (name "R{slash}~{W}") (class "Default")
      (node (ref "IC107") (pin "9") (pinfunction "IN9_9") (pintype "input"))
      (node (ref "IC201") (pin "31") (pinfunction "~{WE}_31") (pintype "input"))
      (node (ref "IC302") (pin "40") (pinfunction "~{WR}_40") (pintype "input"))
      (node (ref "IC502") (pin "23") (pinfunction "~{WR}_23") (pintype "input"))
      (node (ref "SV101") (pin "12") (pinfunction "12_12") (pintype "passive"))
    )
    (net (code "87") (name "UART_CLK") (class "Default")
      (node (ref "IC301") (pin "36") (pinfunction "X1/CLK_36") (pintype "input"))
      (node (ref "IC502") (pin "9") (pinfunction "X1/CLK_9") (pintype "passive"))
      (node (ref "QG301") (pin "5") (pinfunction "OUT_5") (pintype "output"))
    )
    (net (code "88") (name "unconnected-(F501-Pad2)") (class "Default")
      (node (ref "F501") (pin "2") (pinfunction "2_2") (pintype "passive"))
    )
    (net (code "89") (name "unconnected-(F502-Pad2)") (class "Default")
      (node (ref "F502") (pin "2") (pinfunction "2_2") (pintype "passive"))
    )
    (net (code "90") (name "unconnected-(IC102A-A<B_O-Pad7)") (class "Default")
      (node (ref "IC102") (pin "7") (pinfunction "A<B_O_7") (pintype "output"))
    )
    (net (code "91") (name "unconnected-(IC102A-A>B_O-Pad5)") (class "Default")
      (node (ref "IC102") (pin "5") (pinfunction "A>B_O_5") (pintype "output"))
    )
    (net (code "92") (name "unconnected-(IC105A-B1-Pad11)") (class "Default")
      (node (ref "IC105") (pin "11") (pinfunction "B1_11") (pintype "bidirectional"))
    )
    (net (code "93") (name "unconnected-(IC105A-B2-Pad10)") (class "Default")
      (node (ref "IC105") (pin "10") (pinfunction "B2_10") (pintype "bidirectional"))
    )
    (net (code "94") (name "unconnected-(IC105A-B3-Pad9)") (class "Default")
      (node (ref "IC105") (pin "9") (pinfunction "B3_9") (pintype "bidirectional"))
    )
    (net (code "95") (name "unconnected-(IC105A-B4-Pad8)") (class "Default")
      (node (ref "IC105") (pin "8") (pinfunction "B4_8") (pintype "bidirectional"))
    )
    (net (code "96") (name "unconnected-(IC106A-Y7-Pad7)") (class "Default")
      (node (ref "IC106") (pin "7") (pinfunction "Y7_7") (pintype "output"))
    )
    (net (code "97") (name "unconnected-(IC107-IN1{slash}CLK-Pad1)") (class "Default")
      (node (ref "IC107") (pin "1") (pinfunction "IN1/CLK_1") (pintype "input"))
    )
    (net (code "98") (name "unconnected-(IC107-IN2-Pad2)") (class "Default")
      (node (ref "IC107") (pin "2") (pinfunction "IN2_2") (pintype "input"))
    )
    (net (code "99") (name "unconnected-(IC107-IN3-Pad3)") (class "Default")
      (node (ref "IC107") (pin "3") (pinfunction "IN3_3") (pintype "input"))
    )
    (net (code "100") (name "unconnected-(IC107-IO18-Pad18)") (class "Default")
      (node (ref "IC107") (pin "18") (pinfunction "IO18_18") (pintype "bidirectional"))
    )
    (net (code "101") (name "unconnected-(IC107-IO19-Pad19)") (class "Default")
      (node (ref "IC107") (pin "19") (pinfunction "IO19_19") (pintype "bidirectional"))
    )
    (net (code "102") (name "unconnected-(IC107-IO20-Pad20)") (class "Default")
      (node (ref "IC107") (pin "20") (pinfunction "IO20_20") (pintype "bidirectional"))
    )
    (net (code "103") (name "unconnected-(IC107-IO21-Pad21)") (class "Default")
      (node (ref "IC107") (pin "21") (pinfunction "IO21_21") (pintype "bidirectional"))
    )
    (net (code "104") (name "unconnected-(IC107-IO23-Pad23)") (class "Default")
      (node (ref "IC107") (pin "23") (pinfunction "IO23_23") (pintype "bidirectional"))
    )
    (net (code "105") (name "unconnected-(IC301-IP0-Pad8)") (class "Default")
      (node (ref "IC301") (pin "8") (pinfunction "IP0_8") (pintype "input"))
    )
    (net (code "106") (name "unconnected-(IC301-IP1-Pad5)") (class "Default")
      (node (ref "IC301") (pin "5") (pinfunction "IP1_5") (pintype "input"))
    )
    (net (code "107") (name "unconnected-(IC301-IP2-Pad40)") (class "Default")
      (node (ref "IC301") (pin "40") (pinfunction "IP2_40") (pintype "input"))
    )
    (net (code "108") (name "unconnected-(IC301-IP3-Pad3)") (class "Default")
      (node (ref "IC301") (pin "3") (pinfunction "IP3_3") (pintype "input"))
    )
    (net (code "109") (name "unconnected-(IC301-IP4-Pad43)") (class "Default")
      (node (ref "IC301") (pin "43") (pinfunction "IP4_43") (pintype "input"))
    )
    (net (code "110") (name "unconnected-(IC301-IP5-Pad42)") (class "Default")
      (node (ref "IC301") (pin "42") (pinfunction "IP5_42") (pintype "input"))
    )
    (net (code "111") (name "unconnected-(IC301-OP0-Pad32)") (class "Default")
      (node (ref "IC301") (pin "32") (pinfunction "OP0_32") (pintype "output"))
    )
    (net (code "112") (name "unconnected-(IC301-OP1-Pad14)") (class "Default")
      (node (ref "IC301") (pin "14") (pinfunction "OP1_14") (pintype "output"))
    )
    (net (code "113") (name "unconnected-(IC301-OP2-Pad31)") (class "Default")
      (node (ref "IC301") (pin "31") (pinfunction "OP2_31") (pintype "output"))
    )
    (net (code "114") (name "unconnected-(IC301-OP3-Pad15)") (class "Default")
      (node (ref "IC301") (pin "15") (pinfunction "OP3_15") (pintype "output"))
    )
    (net (code "115") (name "unconnected-(IC301-OP4-Pad30)") (class "Default")
      (node (ref "IC301") (pin "30") (pinfunction "OP4_30") (pintype "output"))
    )
    (net (code "116") (name "unconnected-(IC301-OP5-Pad16)") (class "Default")
      (node (ref "IC301") (pin "16") (pinfunction "OP5_16") (pintype "output"))
    )
    (net (code "117") (name "unconnected-(IC301-OP6-Pad29)") (class "Default")
      (node (ref "IC301") (pin "29") (pinfunction "OP6_29") (pintype "output"))
    )
    (net (code "118") (name "unconnected-(IC301-OP7-Pad17)") (class "Default")
      (node (ref "IC301") (pin "17") (pinfunction "OP7_17") (pintype "output"))
    )
    (net (code "119") (name "unconnected-(IC301-R{slash}~{W}-Pad9)") (class "Default")
      (node (ref "IC301") (pin "9") (pinfunction "R/~{W}_9") (pintype "input"))
    )
    (net (code "120") (name "unconnected-(IC301-X2-Pad37)") (class "Default")
      (node (ref "IC301") (pin "37") (pinfunction "X2_37") (pintype "output"))
    )
    (net (code "121") (name "unconnected-(IC302-PA0-Pad5)") (class "Default")
      (node (ref "IC302") (pin "5") (pinfunction "PA0_5") (pintype "bidirectional"))
    )
    (net (code "122") (name "unconnected-(IC302-PA1-Pad4)") (class "Default")
      (node (ref "IC302") (pin "4") (pinfunction "PA1_4") (pintype "bidirectional"))
    )
    (net (code "123") (name "unconnected-(IC302-PA2-Pad3)") (class "Default")
      (node (ref "IC302") (pin "3") (pinfunction "PA2_3") (pintype "bidirectional"))
    )
    (net (code "124") (name "unconnected-(IC302-PA3-Pad2)") (class "Default")
      (node (ref "IC302") (pin "2") (pinfunction "PA3_2") (pintype "bidirectional"))
    )
    (net (code "125") (name "unconnected-(IC302-PA4-Pad44)") (class "Default")
      (node (ref "IC302") (pin "44") (pinfunction "PA4_44") (pintype "bidirectional"))
    )
    (net (code "126") (name "unconnected-(IC302-PA5-Pad43)") (class "Default")
      (node (ref "IC302") (pin "43") (pinfunction "PA5_43") (pintype "bidirectional"))
    )
    (net (code "127") (name "unconnected-(IC302-PA6-Pad42)") (class "Default")
      (node (ref "IC302") (pin "42") (pinfunction "PA6_42") (pintype "bidirectional"))
    )
    (net (code "128") (name "unconnected-(IC302-PA7-Pad41)") (class "Default")
      (node (ref "IC302") (pin "41") (pinfunction "PA7_41") (pintype "bidirectional"))
    )
    (net (code "129") (name "unconnected-(IC302-PB0-Pad20)") (class "Default")
      (node (ref "IC302") (pin "20") (pinfunction "PB0_20") (pintype "bidirectional"))
    )
    (net (code "130") (name "unconnected-(IC302-PB1-Pad21)") (class "Default")
      (node (ref "IC302") (pin "21") (pinfunction "PB1_21") (pintype "bidirectional"))
    )
    (net (code "131") (name "unconnected-(IC302-PB2-Pad22)") (class "Default")
      (node (ref "IC302") (pin "22") (pinfunction "PB2_22") (pintype "bidirectional"))
    )
    (net (code "132") (name "unconnected-(IC302-PB3-Pad24)") (class "Default")
      (node (ref "IC302") (pin "24") (pinfunction "PB3_24") (pintype "bidirectional"))
    )
    (net (code "133") (name "unconnected-(IC302-PB4-Pad25)") (class "Default")
      (node (ref "IC302") (pin "25") (pinfunction "PB4_25") (pintype "bidirectional"))
    )
    (net (code "134") (name "unconnected-(IC302-PB5-Pad26)") (class "Default")
      (node (ref "IC302") (pin "26") (pinfunction "PB5_26") (pintype "bidirectional"))
    )
    (net (code "135") (name "unconnected-(IC302-PB6-Pad27)") (class "Default")
      (node (ref "IC302") (pin "27") (pinfunction "PB6_27") (pintype "bidirectional"))
    )
    (net (code "136") (name "unconnected-(IC302-PB7-Pad28)") (class "Default")
      (node (ref "IC302") (pin "28") (pinfunction "PB7_28") (pintype "bidirectional"))
    )
    (net (code "137") (name "unconnected-(IC302-PC0-Pad16)") (class "Default")
      (node (ref "IC302") (pin "16") (pinfunction "PC0_16") (pintype "bidirectional"))
    )
    (net (code "138") (name "unconnected-(IC302-PC1-Pad17)") (class "Default")
      (node (ref "IC302") (pin "17") (pinfunction "PC1_17") (pintype "bidirectional"))
    )
    (net (code "139") (name "unconnected-(IC302-PC2-Pad18)") (class "Default")
      (node (ref "IC302") (pin "18") (pinfunction "PC2_18") (pintype "bidirectional"))
    )
    (net (code "140") (name "unconnected-(IC302-PC3-Pad19)") (class "Default")
      (node (ref "IC302") (pin "19") (pinfunction "PC3_19") (pintype "bidirectional"))
    )
    (net (code "141") (name "unconnected-(IC302-PC4-Pad15)") (class "Default")
      (node (ref "IC302") (pin "15") (pinfunction "PC4_15") (pintype "bidirectional"))
    )
    (net (code "142") (name "unconnected-(IC302-PC5-Pad14)") (class "Default")
      (node (ref "IC302") (pin "14") (pinfunction "PC5_14") (pintype "bidirectional"))
    )
    (net (code "143") (name "unconnected-(IC302-PC6-Pad13)") (class "Default")
      (node (ref "IC302") (pin "13") (pinfunction "PC6_13") (pintype "bidirectional"))
    )
    (net (code "144") (name "unconnected-(IC302-PC7-Pad11)") (class "Default")
      (node (ref "IC302") (pin "11") (pinfunction "PC7_11") (pintype "bidirectional"))
    )
    (net (code "145") (name "unconnected-(IC501-PB0(ICP)-Pad14)") (class "Default")
      (node (ref "IC501") (pin "14") (pinfunction "PB0(ICP)_14") (pintype "bidirectional"))
    )
    (net (code "146") (name "unconnected-(IC501-PB1(OC1A)-Pad15)") (class "Default")
      (node (ref "IC501") (pin "15") (pinfunction "PB1(OC1A)_15") (pintype "bidirectional"))
    )
    (net (code "147") (name "unconnected-(IC501-PB2(SS{slash}OC1B)-Pad16)") (class "Default")
      (node (ref "IC501") (pin "16") (pinfunction "PB2(SS/OC1B)_16") (pintype "bidirectional"))
    )
    (net (code "148") (name "unconnected-(IC501-PB6(XTAL1{slash}TOSC1)-Pad9)") (class "Default")
      (node (ref "IC501") (pin "9") (pinfunction "PB6(XTAL1/TOSC1)_9") (pintype "bidirectional"))
    )
    (net (code "149") (name "unconnected-(IC501-PB7(XTAL2{slash}TOSC2)-Pad10)") (class "Default")
      (node (ref "IC501") (pin "10") (pinfunction "PB7(XTAL2/TOSC2)_10") (pintype "bidirectional"))
    )
    (net (code "150") (name "unconnected-(IC501-PC0(ADC0)-Pad23)") (class "Default")
      (node (ref "IC501") (pin "23") (pinfunction "PC0(ADC0)_23") (pintype "bidirectional"))
    )
    (net (code "151") (name "unconnected-(IC501-PC1(ADC1)-Pad24)") (class "Default")
      (node (ref "IC501") (pin "24") (pinfunction "PC1(ADC1)_24") (pintype "bidirectional"))
    )
    (net (code "152") (name "unconnected-(IC501-PC2(ADC2)-Pad25)") (class "Default")
      (node (ref "IC501") (pin "25") (pinfunction "PC2(ADC2)_25") (pintype "bidirectional"))
    )
    (net (code "153") (name "unconnected-(IC501-PC3(ADC3)-Pad26)") (class "Default")
      (node (ref "IC501") (pin "26") (pinfunction "PC3(ADC3)_26") (pintype "bidirectional"))
    )
    (net (code "154") (name "unconnected-(IC501-PC4(ADC4{slash}SDA)-Pad27)") (class "Default")
      (node (ref "IC501") (pin "27") (pinfunction "PC4(ADC4/SDA)_27") (pintype "bidirectional"))
    )
    (net (code "155") (name "unconnected-(IC501-PC5(ADC5{slash}SCL)-Pad28)") (class "Default")
      (node (ref "IC501") (pin "28") (pinfunction "PC5(ADC5/SCL)_28") (pintype "bidirectional"))
    )
    (net (code "156") (name "unconnected-(IC501-PD2(INT0)-Pad4)") (class "Default")
      (node (ref "IC501") (pin "4") (pinfunction "PD2(INT0)_4") (pintype "bidirectional"))
    )
    (net (code "157") (name "unconnected-(IC501-PD3(INT1)-Pad5)") (class "Default")
      (node (ref "IC501") (pin "5") (pinfunction "PD3(INT1)_5") (pintype "bidirectional"))
    )
    (net (code "158") (name "unconnected-(IC501-PD4(XCK{slash}T0)-Pad6)") (class "Default")
      (node (ref "IC501") (pin "6") (pinfunction "PD4(XCK/T0)_6") (pintype "bidirectional"))
    )
    (net (code "159") (name "unconnected-(IC501-PD5(T1)-Pad11)") (class "Default")
      (node (ref "IC501") (pin "11") (pinfunction "PD5(T1)_11") (pintype "bidirectional"))
    )
    (net (code "160") (name "unconnected-(IC501-PD6(AIN0)-Pad12)") (class "Default")
      (node (ref "IC501") (pin "12") (pinfunction "PD6(AIN0)_12") (pintype "bidirectional"))
    )
    (net (code "161") (name "unconnected-(IC501-PD7(AIN1)-Pad13)") (class "Default")
      (node (ref "IC501") (pin "13") (pinfunction "PD7(AIN1)_13") (pintype "bidirectional"))
    )
    (net (code "162") (name "unconnected-(IC502-A0-Pad8)") (class "Default")
      (node (ref "IC502") (pin "8") (pinfunction "A0_8") (pintype "input"))
    )
    (net (code "163") (name "unconnected-(IC502-A1-Pad7)") (class "Default")
      (node (ref "IC502") (pin "7") (pinfunction "A1_7") (pintype "input"))
    )
    (net (code "164") (name "unconnected-(IC502-A2-Pad6)") (class "Default")
      (node (ref "IC502") (pin "6") (pinfunction "A2_6") (pintype "input"))
    )
    (net (code "165") (name "unconnected-(IC502-D0-Pad22)") (class "Default")
      (node (ref "IC502") (pin "22") (pinfunction "D0_22") (pintype "bidirectional"))
    )
    (net (code "166") (name "unconnected-(IC502-D1-Pad21)") (class "Default")
      (node (ref "IC502") (pin "21") (pinfunction "D1_21") (pintype "bidirectional"))
    )
    (net (code "167") (name "unconnected-(IC502-D2-Pad20)") (class "Default")
      (node (ref "IC502") (pin "20") (pinfunction "D2_20") (pintype "bidirectional"))
    )
    (net (code "168") (name "unconnected-(IC502-D3-Pad19)") (class "Default")
      (node (ref "IC502") (pin "19") (pinfunction "D3_19") (pintype "bidirectional"))
    )
    (net (code "169") (name "unconnected-(IC502-D4-Pad18)") (class "Default")
      (node (ref "IC502") (pin "18") (pinfunction "D4_18") (pintype "bidirectional"))
    )
    (net (code "170") (name "unconnected-(IC502-D5-Pad17)") (class "Default")
      (node (ref "IC502") (pin "17") (pinfunction "D5_17") (pintype "bidirectional"))
    )
    (net (code "171") (name "unconnected-(IC502-D6-Pad16)") (class "Default")
      (node (ref "IC502") (pin "16") (pinfunction "D6_16") (pintype "bidirectional"))
    )
    (net (code "172") (name "unconnected-(IC502-D7-Pad15)") (class "Default")
      (node (ref "IC502") (pin "15") (pinfunction "D7_15") (pintype "bidirectional"))
    )
    (net (code "173") (name "unconnected-(IC502-MPI-Pad5)") (class "Default")
      (node (ref "IC502") (pin "5") (pinfunction "MPI_5") (pintype "input"))
    )
    (net (code "174") (name "unconnected-(IC502-MPO-Pad4)") (class "Default")
      (node (ref "IC502") (pin "4") (pinfunction "MPO_4") (pintype "output"))
    )
    (net (code "175") (name "unconnected-(IC502-X2-Pad10)") (class "Default")
      (node (ref "IC502") (pin "10") (pinfunction "X2_10") (pintype "passive"))
    )
    (net (code "176") (name "unconnected-(QG301-TS-Pad1)") (class "Default")
      (node (ref "QG301") (pin "1") (pinfunction "TS_1") (pintype "passive"))
    )
    (net (code "177") (name "unconnected-(SV101-Pad5)") (class "Default")
      (node (ref "SV101") (pin "5") (pinfunction "5_5") (pintype "passive"))
    )
    (net (code "178") (name "unconnected-(SV101-Pad7)") (class "Default")
      (node (ref "SV101") (pin "7") (pinfunction "7_7") (pintype "passive"))
    )
    (net (code "179") (name "unconnected-(SV101-Pad8)") (class "Default")
      (node (ref "SV101") (pin "8") (pinfunction "8_8") (pintype "passive"))
    )
    (net (code "180") (name "unconnected-(SV101-Pad9)") (class "Default")
      (node (ref "SV101") (pin "9") (pinfunction "9_9") (pintype "passive"))
    )
    (net (code "181") (name "unconnected-(SV101-Pad14)") (class "Default")
      (node (ref "SV101") (pin "14") (pinfunction "14_14") (pintype "passive"))
    )
    (net (code "182") (name "unconnected-(SV101-Pad15)") (class "Default")
      (node (ref "SV101") (pin "15") (pinfunction "15_15") (pintype "passive"))
    )
    (net (code "183") (name "unconnected-(SV101-Pad43)") (class "Default")
      (node (ref "SV101") (pin "43") (pinfunction "43_43") (pintype "passive"))
    )
    (net (code "184") (name "unconnected-(SV101-Pad44)") (class "Default")
      (node (ref "SV101") (pin "44") (pinfunction "44_44") (pintype "passive"))
    )
    (net (code "185") (name "unconnected-(SV101-Pad47)") (class "Default")
      (node (ref "SV101") (pin "47") (pinfunction "47_47") (pintype "passive"))
    )
    (net (code "186") (name "unconnected-(SV101-Pad49)") (class "Default")
      (node (ref "SV101") (pin "49") (pinfunction "49_49") (pintype "passive"))
    )
    (net (code "187") (name "unconnected-(SV101-Pad51)") (class "Default")
      (node (ref "SV101") (pin "51") (pinfunction "51_51") (pintype "passive"))
    )
    (net (code "188") (name "unconnected-(SV101-Pad53)") (class "Default")
      (node (ref "SV101") (pin "53") (pinfunction "53_53") (pintype "passive"))
    )
    (net (code "189") (name "unconnected-(SV101-Pad55)") (class "Default")
      (node (ref "SV101") (pin "55") (pinfunction "55_55") (pintype "passive"))
    )
    (net (code "190") (name "unconnected-(SV101-Pad57)") (class "Default")
      (node (ref "SV101") (pin "57") (pinfunction "57_57") (pintype "passive"))
    )
    (net (code "191") (name "unconnected-(SV101-Pad59)") (class "Default")
      (node (ref "SV101") (pin "59") (pinfunction "59_59") (pintype "passive"))
    )
    (net (code "192") (name "unconnected-(SV101-Pad61)") (class "Default")
      (node (ref "SV101") (pin "61") (pinfunction "61_61") (pintype "passive"))
    )
    (net (code "193") (name "unconnected-(SV401-Pad1)") (class "Default")
      (node (ref "SV401") (pin "1") (pinfunction "1_1") (pintype "passive"))
    )
    (net (code "194") (name "unconnected-(SV401-Pad2)") (class "Default")
      (node (ref "SV401") (pin "2") (pinfunction "2_2") (pintype "passive"))
    )
    (net (code "195") (name "unconnected-(SV401-Pad3)") (class "Default")
      (node (ref "SV401") (pin "3") (pinfunction "3_3") (pintype "passive"))
    )
    (net (code "196") (name "unconnected-(SV401-Pad4)") (class "Default")
      (node (ref "SV401") (pin "4") (pinfunction "4_4") (pintype "passive"))
    )
    (net (code "197") (name "unconnected-(SV401-Pad5)") (class "Default")
      (node (ref "SV401") (pin "5") (pinfunction "5_5") (pintype "passive"))
    )
    (net (code "198") (name "unconnected-(SV401-Pad6)") (class "Default")
      (node (ref "SV401") (pin "6") (pinfunction "6_6") (pintype "passive"))
    )
    (net (code "199") (name "unconnected-(SV401-Pad7)") (class "Default")
      (node (ref "SV401") (pin "7") (pinfunction "7_7") (pintype "passive"))
    )
    (net (code "200") (name "unconnected-(SV401-Pad8)") (class "Default")
      (node (ref "SV401") (pin "8") (pinfunction "8_8") (pintype "passive"))
    )
    (net (code "201") (name "unconnected-(SV401-Pad9)") (class "Default")
      (node (ref "SV401") (pin "9") (pinfunction "9_9") (pintype "passive"))
    )
    (net (code "202") (name "unconnected-(SV401-Pad10)") (class "Default")
      (node (ref "SV401") (pin "10") (pinfunction "10_10") (pintype "passive"))
    )
    (net (code "203") (name "unconnected-(SV401-Pad11)") (class "Default")
      (node (ref "SV401") (pin "11") (pinfunction "11_11") (pintype "passive"))
    )
    (net (code "204") (name "unconnected-(SV401-Pad12)") (class "Default")
      (node (ref "SV401") (pin "12") (pinfunction "12_12") (pintype "passive"))
    )
    (net (code "205") (name "unconnected-(SV401-Pad13)") (class "Default")
      (node (ref "SV401") (pin "13") (pinfunction "13_13") (pintype "passive"))
    )
    (net (code "206") (name "unconnected-(SV401-Pad14)") (class "Default")
      (node (ref "SV401") (pin "14") (pinfunction "14_14") (pintype "passive"))
    )
    (net (code "207") (name "unconnected-(SV401-Pad15)") (class "Default")
      (node (ref "SV401") (pin "15") (pinfunction "15_15") (pintype "passive"))
    )
    (net (code "208") (name "unconnected-(SV401-Pad16)") (class "Default")
      (node (ref "SV401") (pin "16") (pinfunction "16_16") (pintype "passive"))
    )
    (net (code "209") (name "unconnected-(SV401-Pad17)") (class "Default")
      (node (ref "SV401") (pin "17") (pinfunction "17_17") (pintype "passive"))
    )
    (net (code "210") (name "unconnected-(SV401-Pad18)") (class "Default")
      (node (ref "SV401") (pin "18") (pinfunction "18_18") (pintype "passive"))
    )
    (net (code "211") (name "unconnected-(SV401-Pad19)") (class "Default")
      (node (ref "SV401") (pin "19") (pinfunction "19_19") (pintype "passive"))
    )
    (net (code "212") (name "unconnected-(SV401-Pad20)") (class "Default")
      (node (ref "SV401") (pin "20") (pinfunction "20_20") (pintype "passive"))
    )
    (net (code "213") (name "unconnected-(SV401-Pad21)") (class "Default")
      (node (ref "SV401") (pin "21") (pinfunction "21_21") (pintype "passive"))
    )
    (net (code "214") (name "unconnected-(SV401-Pad22)") (class "Default")
      (node (ref "SV401") (pin "22") (pinfunction "22_22") (pintype "passive"))
    )
    (net (code "215") (name "unconnected-(SV401-Pad23)") (class "Default")
      (node (ref "SV401") (pin "23") (pinfunction "23_23") (pintype "passive"))
    )
    (net (code "216") (name "unconnected-(SV401-Pad24)") (class "Default")
      (node (ref "SV401") (pin "24") (pinfunction "24_24") (pintype "passive"))
    )
    (net (code "217") (name "unconnected-(SV401-Pad25)") (class "Default")
      (node (ref "SV401") (pin "25") (pinfunction "25_25") (pintype "passive"))
    )
    (net (code "218") (name "unconnected-(SV401-Pad26)") (class "Default")
      (node (ref "SV401") (pin "26") (pinfunction "26_26") (pintype "passive"))
    )
    (net (code "219") (name "unconnected-(SV401-Pad27)") (class "Default")
      (node (ref "SV401") (pin "27") (pinfunction "27_27") (pintype "passive"))
    )
    (net (code "220") (name "unconnected-(SV401-Pad28)") (class "Default")
      (node (ref "SV401") (pin "28") (pinfunction "28_28") (pintype "passive"))
    )
    (net (code "221") (name "unconnected-(SV401-Pad29)") (class "Default")
      (node (ref "SV401") (pin "29") (pinfunction "29_29") (pintype "passive"))
    )
    (net (code "222") (name "unconnected-(SV401-Pad30)") (class "Default")
      (node (ref "SV401") (pin "30") (pinfunction "30_30") (pintype "passive"))
    )
    (net (code "223") (name "unconnected-(SV401-Pad31)") (class "Default")
      (node (ref "SV401") (pin "31") (pinfunction "31_31") (pintype "passive"))
    )
    (net (code "224") (name "unconnected-(SV401-Pad32)") (class "Default")
      (node (ref "SV401") (pin "32") (pinfunction "32_32") (pintype "passive"))
    )
    (net (code "225") (name "unconnected-(SV401-Pad33)") (class "Default")
      (node (ref "SV401") (pin "33") (pinfunction "33_33") (pintype "passive"))
    )
    (net (code "226") (name "unconnected-(SV401-Pad34)") (class "Default")
      (node (ref "SV401") (pin "34") (pinfunction "34_34") (pintype "passive"))
    )
    (net (code "227") (name "unconnected-(SV401-Pad35)") (class "Default")
      (node (ref "SV401") (pin "35") (pinfunction "35_35") (pintype "passive"))
    )
    (net (code "228") (name "unconnected-(SV401-Pad36)") (class "Default")
      (node (ref "SV401") (pin "36") (pinfunction "36_36") (pintype "passive"))
    )
    (net (code "229") (name "unconnected-(SV401-Pad37)") (class "Default")
      (node (ref "SV401") (pin "37") (pinfunction "37_37") (pintype "passive"))
    )
    (net (code "230") (name "unconnected-(SV401-Pad38)") (class "Default")
      (node (ref "SV401") (pin "38") (pinfunction "38_38") (pintype "passive"))
    )
    (net (code "231") (name "unconnected-(SV401-Pad39)") (class "Default")
      (node (ref "SV401") (pin "39") (pinfunction "39_39") (pintype "passive"))
    )
    (net (code "232") (name "unconnected-(SV401-Pad40)") (class "Default")
      (node (ref "SV401") (pin "40") (pinfunction "40_40") (pintype "passive"))
    )
    (net (code "233") (name "~{68681_IRQ}") (class "Default")
      (node (ref "IC301") (pin "24") (pinfunction "~{INTR}_24") (pintype "output"))
      (node (ref "R301") (pin "1") (pinfunction "1_1") (pintype "passive"))
    )
    (net (code "234") (name "~{AS}") (class "Default")
      (node (ref "IC107") (pin "11") (pinfunction "IN11_11") (pintype "input"))
      (node (ref "SV101") (pin "13") (pinfunction "13_13") (pintype "passive"))
    )
    (net (code "235") (name "~{ATA_CS}") (class "Default")
      (node (ref "IC106") (pin "14") (pinfunction "Y1_14") (pintype "output"))
    )
    (net (code "236") (name "~{AVR_RESET}") (class "Default")
      (node (ref "IC501") (pin "1") (pinfunction "PC6(/RESET)_1") (pintype "bidirectional"))
      (node (ref "SV501") (pin "2") (pinfunction "2_2") (pintype "passive"))
    )
    (net (code "237") (name "~{A_CTS}") (class "Default")
      (node (ref "SV301") (pin "1") (pinfunction "1_1") (pintype "passive"))
      (node (ref "SV301") (pin "9") (pinfunction "9_9") (pintype "passive"))
    )
    (net (code "238") (name "~{B_CTS}") (class "Default")
      (node (ref "SV301") (pin "10") (pinfunction "10_10") (pintype "passive"))
      (node (ref "SV301") (pin "2") (pinfunction "2_2") (pintype "passive"))
    )
    (net (code "239") (name "~{CS}") (class "Default")
      (node (ref "IC101") (pin "19") (pinfunction "G_19") (pintype "input"))
      (node (ref "IC103") (pin "19") (pinfunction "G_19") (pintype "input"))
      (node (ref "IC104") (pin "19") (pinfunction "G_19") (pintype "input"))
      (node (ref "IC105") (pin "1") (pinfunction "GAB_1") (pintype "input"))
      (node (ref "IC106") (pin "4") (pinfunction "G2A_4") (pintype "input"))
      (node (ref "IC107") (pin "14") (pinfunction "IO14_14") (pintype "bidirectional"))
    )
    (net (code "240") (name "~{DTACK}") (class "Default")
      (node (ref "IC107") (pin "16") (pinfunction "IO16_16") (pintype "bidirectional"))
      (node (ref "IC301") (pin "10") (pinfunction "~{DTACK}_10") (pintype "output"))
      (node (ref "SV101") (pin "10") (pinfunction "10_10") (pintype "passive"))
    )
    (net (code "241") (name "~{DUART_CS}") (class "Default")
      (node (ref "IC106") (pin "15") (pinfunction "Y0_15") (pintype "output"))
      (node (ref "IC301") (pin "39") (pinfunction "~{CS}_39") (pintype "input"))
    )
    (net (code "242") (name "~{EXTI_A}") (class "Default")
      (node (ref "IC107") (pin "17") (pinfunction "IO17_17") (pintype "bidirectional"))
      (node (ref "SV101") (pin "16") (pinfunction "16_16") (pintype "passive"))
    )
    (net (code "243") (name "~{EXT_ID}") (class "Default")
      (node (ref "IC107") (pin "6") (pinfunction "IN6_6") (pintype "input"))
      (node (ref "SV101") (pin "41") (pinfunction "41_41") (pintype "passive"))
    )
    (net (code "244") (name "~{I2C_CS}") (class "Default")
      (node (ref "IC106") (pin "9") (pinfunction "Y6_9") (pintype "output"))
    )
    (net (code "245") (name "~{LCD_CS}") (class "Default")
      (node (ref "IC106") (pin "11") (pinfunction "Y4_11") (pintype "output"))
    )
    (net (code "246") (name "~{LDS}") (class "Default")
      (node (ref "IC107") (pin "10") (pinfunction "IN10_10") (pintype "input"))
      (node (ref "SV101") (pin "11") (pinfunction "11_11") (pintype "passive"))
    )
    (net (code "247") (name "~{PIO_CS}") (class "Default")
      (node (ref "IC106") (pin "12") (pinfunction "Y3_12") (pintype "output"))
      (node (ref "IC302") (pin "7") (pinfunction "~{CS}_7") (pintype "input"))
    )
    (net (code "248") (name "~{PS2_CS}") (class "Default")
      (node (ref "IC106") (pin "13") (pinfunction "Y2_13") (pintype "output"))
      (node (ref "IC502") (pin "14") (pinfunction "~{CS}_14") (pintype "input"))
    )
    (net (code "249") (name "~{PS2_IRQ}") (class "Default")
      (node (ref "IC502") (pin "13") (pinfunction "~{IRQ}_13") (pintype "output"))
    )
    (net (code "250") (name "~{RD}") (class "Default")
      (node (ref "IC101") (pin "1") (pinfunction "DIR_1") (pintype "input"))
      (node (ref "IC107") (pin "15") (pinfunction "IO15_15") (pintype "bidirectional"))
      (node (ref "IC201") (pin "24") (pinfunction "~{OE}_24") (pintype "input"))
      (node (ref "IC302") (pin "6") (pinfunction "~{RD}_6") (pintype "input"))
      (node (ref "IC502") (pin "1") (pinfunction "~{RD}_1") (pintype "input"))
    )
    (net (code "251") (name "~{RESET}") (class "Default")
      (node (ref "IC107") (pin "8") (pinfunction "IN8_8") (pintype "input"))
      (node (ref "IC301") (pin "38") (pinfunction "~{RESET}_38") (pintype "input"))
      (node (ref "SV101") (pin "6") (pinfunction "6_6") (pintype "passive"))
    )
    (net (code "252") (name "~{ROM_CS}") (class "Default")
      (node (ref "IC106") (pin "6") (pinfunction "G1_6") (pintype "input"))
      (node (ref "IC107") (pin "22") (pinfunction "IO22_22") (pintype "bidirectional"))
      (node (ref "IC201") (pin "22") (pinfunction "~{CS}_22") (pintype "input"))
    )
    (net (code "253") (name "~{STATUS_CS}") (class "Default")
      (node (ref "IC106") (pin "10") (pinfunction "Y5_10") (pintype "output"))
    )
  )
)
